# GS_01_Core.net
KiCad netlist of a schematic drawn in Altium Designer
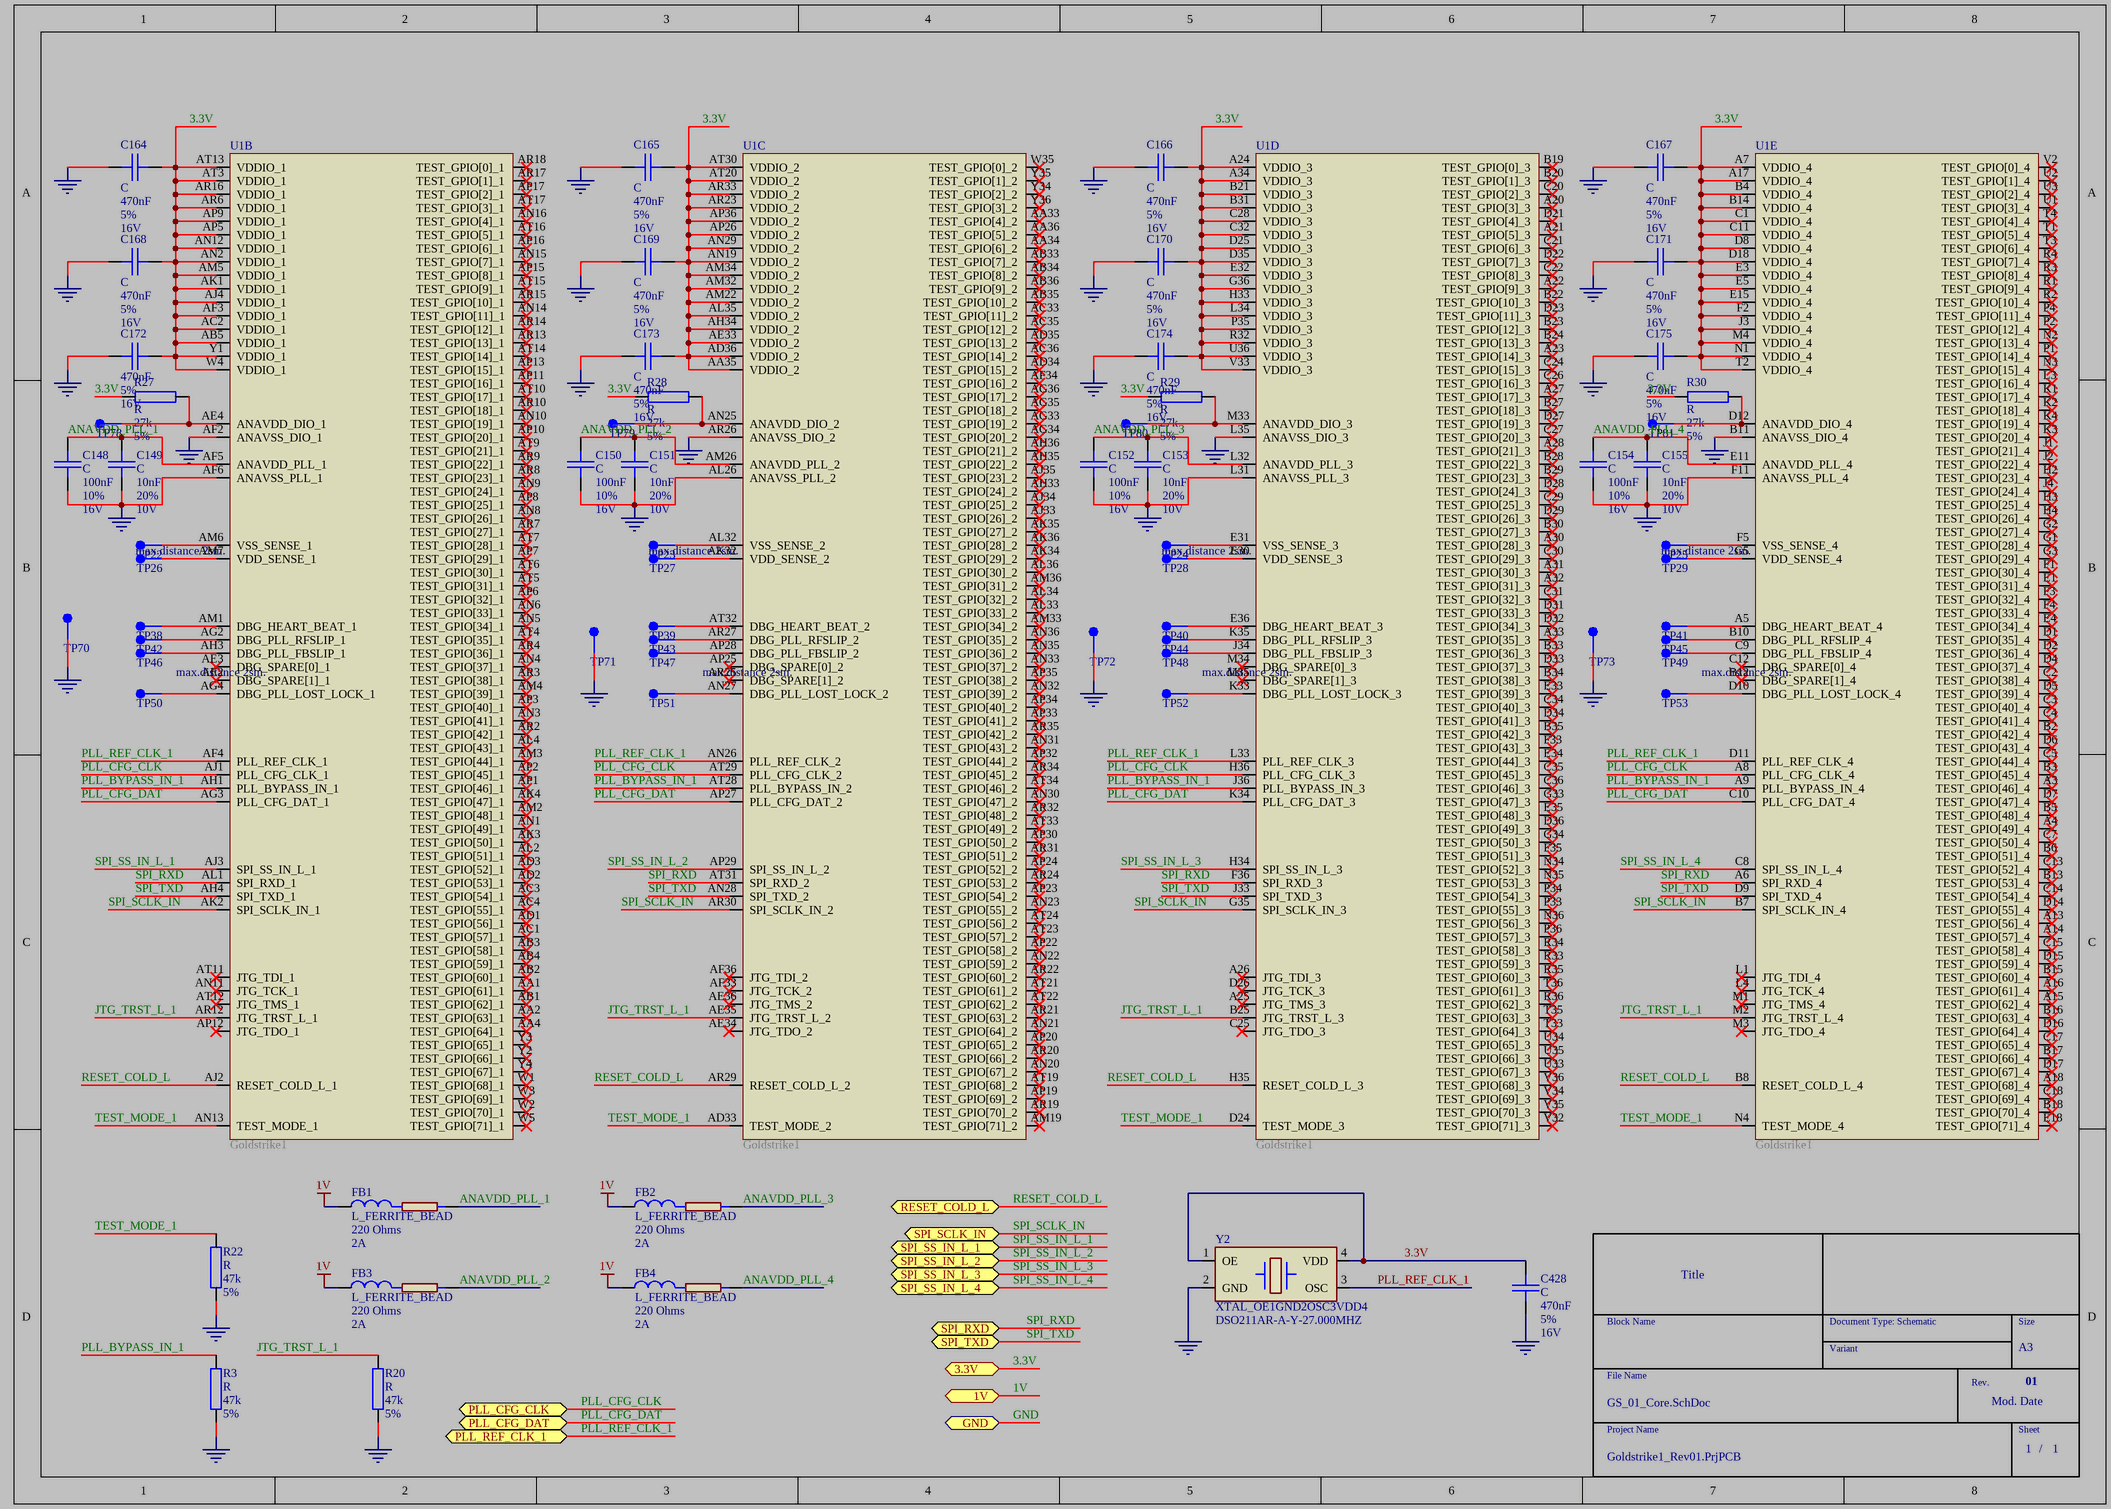
[diagram p0: GS_01_Core.SchDoc]

(export (version "E")
  (design (tool "Eeschema 10.0.6"))
  (components
    (comp (ref "C148")
      (value "C")
      (footprint "SMD_0603_CAPC1608X95N")
      (fields
        (field (name "DB_PART_NUMBER") "CAP000047357")
        (field (name "DB_VALUE") "100nF")
        (field (name "DB_TOLERANCE") "10%")
        (field (name "DB_VOLTAGE") "16V")
        (field (name "DB_MANUFACTURER_PART") "YAGEO      223878615649")
        (field (name "DB_APPROVED_BY") "VSN")
      )
      (libsource (lib "Database_Libs1") (part "C"))
    )
    (comp (ref "C149")
      (value "C")
      (footprint "SMD_0603_CAPC1608X95N")
      (fields
        (field (name "DB_PART_NUMBER") "CAP000038821")
        (field (name "DB_VALUE") "10nF")
        (field (name "DB_TOLERANCE") "20%")
        (field (name "DB_VOLTAGE") "10V")
        (field (name "DB_MANUFACTURER_PART") "KEMET    C0603C103M8GAC")
      )
      (libsource (lib "Database_Libs1") (part "C"))
    )
    (comp (ref "C150")
      (value "C")
      (footprint "SMD_0603_CAPC1608X95N")
      (fields
        (field (name "DB_PART_NUMBER") "CAP000047357")
        (field (name "DB_VALUE") "100nF")
        (field (name "DB_TOLERANCE") "10%")
        (field (name "DB_VOLTAGE") "16V")
        (field (name "DB_MANUFACTURER_PART") "YAGEO      223878615649")
        (field (name "DB_APPROVED_BY") "VSN")
      )
      (libsource (lib "Database_Libs1") (part "C"))
    )
    (comp (ref "C151")
      (value "C")
      (footprint "SMD_0603_CAPC1608X95N")
      (fields
        (field (name "DB_PART_NUMBER") "CAP000038821")
        (field (name "DB_VALUE") "10nF")
        (field (name "DB_TOLERANCE") "20%")
        (field (name "DB_VOLTAGE") "10V")
        (field (name "DB_MANUFACTURER_PART") "KEMET    C0603C103M8GAC")
      )
      (libsource (lib "Database_Libs1") (part "C"))
    )
    (comp (ref "C152")
      (value "C")
      (footprint "SMD_0603_CAPC1608X95N")
      (fields
        (field (name "DB_PART_NUMBER") "CAP000047357")
        (field (name "DB_VALUE") "100nF")
        (field (name "DB_TOLERANCE") "10%")
        (field (name "DB_VOLTAGE") "16V")
        (field (name "DB_MANUFACTURER_PART") "YAGEO      223878615649")
        (field (name "DB_APPROVED_BY") "VSN")
      )
      (libsource (lib "Database_Libs1") (part "C"))
    )
    (comp (ref "C153")
      (value "C")
      (footprint "SMD_0603_CAPC1608X95N")
      (fields
        (field (name "DB_PART_NUMBER") "CAP000038821")
        (field (name "DB_VALUE") "10nF")
        (field (name "DB_TOLERANCE") "20%")
        (field (name "DB_VOLTAGE") "10V")
        (field (name "DB_MANUFACTURER_PART") "KEMET    C0603C103M8GAC")
      )
      (libsource (lib "Database_Libs1") (part "C"))
    )
    (comp (ref "C154")
      (value "C")
      (footprint "SMD_0603_CAPC1608X95N")
      (fields
        (field (name "DB_PART_NUMBER") "CAP000047357")
        (field (name "DB_VALUE") "100nF")
        (field (name "DB_TOLERANCE") "10%")
        (field (name "DB_VOLTAGE") "16V")
        (field (name "DB_MANUFACTURER_PART") "YAGEO      223878615649")
        (field (name "DB_APPROVED_BY") "VSN")
      )
      (libsource (lib "Database_Libs1") (part "C"))
    )
    (comp (ref "C155")
      (value "C")
      (footprint "SMD_0603_CAPC1608X95N")
      (fields
        (field (name "DB_PART_NUMBER") "CAP000038821")
        (field (name "DB_VALUE") "10nF")
        (field (name "DB_TOLERANCE") "20%")
        (field (name "DB_VOLTAGE") "10V")
        (field (name "DB_MANUFACTURER_PART") "KEMET    C0603C103M8GAC")
      )
      (libsource (lib "Database_Libs1") (part "C"))
    )
    (comp (ref "C164")
      (value "C")
      (footprint "SMD_0603_CAPC1608X95N")
      (fields
        (field (name "DB_PART_NUMBER") "CAP000028169")
        (field (name "DB_VALUE") "470nF")
        (field (name "DB_TOLERANCE") "5%")
        (field (name "DB_VOLTAGE") "16V")
        (field (name "DB_MANUFACTURER_PART") "KEMET    C0603C474J4RAC")
      )
      (libsource (lib "Database_Libs1") (part "C"))
    )
    (comp (ref "C165")
      (value "C")
      (footprint "SMD_0603_CAPC1608X95N")
      (fields
        (field (name "DB_PART_NUMBER") "CAP000028169")
        (field (name "DB_VALUE") "470nF")
        (field (name "DB_TOLERANCE") "5%")
        (field (name "DB_VOLTAGE") "16V")
        (field (name "DB_MANUFACTURER_PART") "KEMET    C0603C474J4RAC")
      )
      (libsource (lib "Database_Libs1") (part "C"))
    )
    (comp (ref "C166")
      (value "C")
      (footprint "SMD_0603_CAPC1608X95N")
      (fields
        (field (name "DB_PART_NUMBER") "CAP000028169")
        (field (name "DB_VALUE") "470nF")
        (field (name "DB_TOLERANCE") "5%")
        (field (name "DB_VOLTAGE") "16V")
        (field (name "DB_MANUFACTURER_PART") "KEMET    C0603C474J4RAC")
      )
      (libsource (lib "Database_Libs1") (part "C"))
    )
    (comp (ref "C167")
      (value "C")
      (footprint "SMD_0603_CAPC1608X95N")
      (fields
        (field (name "DB_PART_NUMBER") "CAP000028169")
        (field (name "DB_VALUE") "470nF")
        (field (name "DB_TOLERANCE") "5%")
        (field (name "DB_VOLTAGE") "16V")
        (field (name "DB_MANUFACTURER_PART") "KEMET    C0603C474J4RAC")
      )
      (libsource (lib "Database_Libs1") (part "C"))
    )
    (comp (ref "C168")
      (value "C")
      (footprint "SMD_0603_CAPC1608X95N")
      (fields
        (field (name "DB_PART_NUMBER") "CAP000028169")
        (field (name "DB_VALUE") "470nF")
        (field (name "DB_TOLERANCE") "5%")
        (field (name "DB_VOLTAGE") "16V")
        (field (name "DB_MANUFACTURER_PART") "KEMET    C0603C474J4RAC")
      )
      (libsource (lib "Database_Libs1") (part "C"))
    )
    (comp (ref "C169")
      (value "C")
      (footprint "SMD_0603_CAPC1608X95N")
      (fields
        (field (name "DB_PART_NUMBER") "CAP000028169")
        (field (name "DB_VALUE") "470nF")
        (field (name "DB_TOLERANCE") "5%")
        (field (name "DB_VOLTAGE") "16V")
        (field (name "DB_MANUFACTURER_PART") "KEMET    C0603C474J4RAC")
      )
      (libsource (lib "Database_Libs1") (part "C"))
    )
    (comp (ref "C170")
      (value "C")
      (footprint "SMD_0603_CAPC1608X95N")
      (fields
        (field (name "DB_PART_NUMBER") "CAP000028169")
        (field (name "DB_VALUE") "470nF")
        (field (name "DB_TOLERANCE") "5%")
        (field (name "DB_VOLTAGE") "16V")
        (field (name "DB_MANUFACTURER_PART") "KEMET    C0603C474J4RAC")
      )
      (libsource (lib "Database_Libs1") (part "C"))
    )
    (comp (ref "C171")
      (value "C")
      (footprint "SMD_0603_CAPC1608X95N")
      (fields
        (field (name "DB_PART_NUMBER") "CAP000028169")
        (field (name "DB_VALUE") "470nF")
        (field (name "DB_TOLERANCE") "5%")
        (field (name "DB_VOLTAGE") "16V")
        (field (name "DB_MANUFACTURER_PART") "KEMET    C0603C474J4RAC")
      )
      (libsource (lib "Database_Libs1") (part "C"))
    )
    (comp (ref "C172")
      (value "C")
      (footprint "SMD_0603_CAPC1608X95N")
      (fields
        (field (name "DB_PART_NUMBER") "CAP000028169")
        (field (name "DB_VALUE") "470nF")
        (field (name "DB_TOLERANCE") "5%")
        (field (name "DB_VOLTAGE") "16V")
        (field (name "DB_MANUFACTURER_PART") "KEMET    C0603C474J4RAC")
      )
      (libsource (lib "Database_Libs1") (part "C"))
    )
    (comp (ref "C173")
      (value "C")
      (footprint "SMD_0603_CAPC1608X95N")
      (fields
        (field (name "DB_PART_NUMBER") "CAP000028169")
        (field (name "DB_VALUE") "470nF")
        (field (name "DB_TOLERANCE") "5%")
        (field (name "DB_VOLTAGE") "16V")
        (field (name "DB_MANUFACTURER_PART") "KEMET    C0603C474J4RAC")
      )
      (libsource (lib "Database_Libs1") (part "C"))
    )
    (comp (ref "C174")
      (value "C")
      (footprint "SMD_0603_CAPC1608X95N")
      (fields
        (field (name "DB_PART_NUMBER") "CAP000028169")
        (field (name "DB_VALUE") "470nF")
        (field (name "DB_TOLERANCE") "5%")
        (field (name "DB_VOLTAGE") "16V")
        (field (name "DB_MANUFACTURER_PART") "KEMET    C0603C474J4RAC")
      )
      (libsource (lib "Database_Libs1") (part "C"))
    )
    (comp (ref "C175")
      (value "C")
      (footprint "SMD_0603_CAPC1608X95N")
      (fields
        (field (name "DB_PART_NUMBER") "CAP000028169")
        (field (name "DB_VALUE") "470nF")
        (field (name "DB_TOLERANCE") "5%")
        (field (name "DB_VOLTAGE") "16V")
        (field (name "DB_MANUFACTURER_PART") "KEMET    C0603C474J4RAC")
      )
      (libsource (lib "Database_Libs1") (part "C"))
    )
    (comp (ref "C428")
      (value "C")
      (footprint "SMD_0603_CAPC1608X95N")
      (fields
        (field (name "DB_PART_NUMBER") "CAP000028169")
        (field (name "DB_VALUE") "470nF")
        (field (name "DB_TOLERANCE") "5%")
        (field (name "DB_VOLTAGE") "16V")
        (field (name "DB_MANUFACTURER_PART") "KEMET    C0603C474J4RAC")
      )
      (libsource (lib "Database_Libs1") (part "C"))
    )
    (comp (ref "FB1")
      (value "L_FERRITE_BEAD")
      (footprint "SMD_0805_INDC2012X105N")
      (fields
        (field (name "DB_PART_NUMBER") "IND000000029")
        (field (name "DB_VALUE") "220 Ohms")
        (field (name "DB_CURRENT") "2A")
        (field (name "DB_MANUFACTURER_PART") "MURATA       BLM21PG221SN1D")
        (field (name "DB_APPROVED_BY") "VSN")
      )
      (libsource (lib "Database_Libs1") (part "L_FERRITE_BEAD"))
    )
    (comp (ref "FB2")
      (value "L_FERRITE_BEAD")
      (footprint "SMD_0805_INDC2012X105N")
      (fields
        (field (name "DB_PART_NUMBER") "IND000000029")
        (field (name "DB_VALUE") "220 Ohms")
        (field (name "DB_CURRENT") "2A")
        (field (name "DB_MANUFACTURER_PART") "MURATA       BLM21PG221SN1D")
        (field (name "DB_APPROVED_BY") "VSN")
      )
      (libsource (lib "Database_Libs1") (part "L_FERRITE_BEAD"))
    )
    (comp (ref "FB3")
      (value "L_FERRITE_BEAD")
      (footprint "SMD_0805_INDC2012X105N")
      (fields
        (field (name "DB_PART_NUMBER") "IND000000029")
        (field (name "DB_VALUE") "220 Ohms")
        (field (name "DB_CURRENT") "2A")
        (field (name "DB_MANUFACTURER_PART") "MURATA       BLM21PG221SN1D")
        (field (name "DB_APPROVED_BY") "VSN")
      )
      (libsource (lib "Database_Libs1") (part "L_FERRITE_BEAD"))
    )
    (comp (ref "FB4")
      (value "L_FERRITE_BEAD")
      (footprint "SMD_0805_INDC2012X105N")
      (fields
        (field (name "DB_PART_NUMBER") "IND000000029")
        (field (name "DB_VALUE") "220 Ohms")
        (field (name "DB_CURRENT") "2A")
        (field (name "DB_MANUFACTURER_PART") "MURATA       BLM21PG221SN1D")
        (field (name "DB_APPROVED_BY") "VSN")
      )
      (libsource (lib "Database_Libs1") (part "L_FERRITE_BEAD"))
    )
    (comp (ref "R3")
      (value "R")
      (footprint "SMD_0603_RESC1608X55N")
      (fields
        (field (name "DB_PART_NUMBER") "RES000006462")
        (field (name "DB_VALUE") "47k")
        (field (name "DB_TOLERANCE") "5%")
        (field (name "DB_MANUFACTURER_PART") "YAGEO    RC0603JR-0747K")
      )
      (libsource (lib "Database_Libs1") (part "R"))
    )
    (comp (ref "R20")
      (value "R")
      (footprint "SMD_0603_RESC1608X55N")
      (fields
        (field (name "DB_PART_NUMBER") "RES000006462")
        (field (name "DB_VALUE") "47k")
        (field (name "DB_TOLERANCE") "5%")
        (field (name "DB_MANUFACTURER_PART") "YAGEO    RC0603JR-0747K")
      )
      (libsource (lib "Database_Libs1") (part "R"))
    )
    (comp (ref "R22")
      (value "R")
      (footprint "SMD_0603_RESC1608X55N")
      (fields
        (field (name "DB_PART_NUMBER") "RES000006462")
        (field (name "DB_VALUE") "47k")
        (field (name "DB_TOLERANCE") "5%")
        (field (name "DB_MANUFACTURER_PART") "YAGEO    RC0603JR-0747K")
      )
      (libsource (lib "Database_Libs1") (part "R"))
    )
    (comp (ref "R27")
      (value "R")
      (footprint "SMD_0603_RESC1608X55N")
      (fields
        (field (name "DB_PART_NUMBER") "RES000006456")
        (field (name "DB_VALUE") "27k")
        (field (name "DB_TOLERANCE") "5%")
        (field (name "DB_MANUFACTURER_PART") "YAGEO    RC0603JR-0727K")
      )
      (libsource (lib "Database_Libs1") (part "R"))
    )
    (comp (ref "R28")
      (value "R")
      (footprint "SMD_0603_RESC1608X55N")
      (fields
        (field (name "DB_PART_NUMBER") "RES000006456")
        (field (name "DB_VALUE") "27k")
        (field (name "DB_TOLERANCE") "5%")
        (field (name "DB_MANUFACTURER_PART") "YAGEO    RC0603JR-0727K")
      )
      (libsource (lib "Database_Libs1") (part "R"))
    )
    (comp (ref "R29")
      (value "R")
      (footprint "SMD_0603_RESC1608X55N")
      (fields
        (field (name "DB_PART_NUMBER") "RES000006456")
        (field (name "DB_VALUE") "27k")
        (field (name "DB_TOLERANCE") "5%")
        (field (name "DB_MANUFACTURER_PART") "YAGEO    RC0603JR-0727K")
      )
      (libsource (lib "Database_Libs1") (part "R"))
    )
    (comp (ref "R30")
      (value "R")
      (footprint "SMD_0603_RESC1608X55N")
      (fields
        (field (name "DB_PART_NUMBER") "RES000006456")
        (field (name "DB_VALUE") "27k")
        (field (name "DB_TOLERANCE") "5%")
        (field (name "DB_MANUFACTURER_PART") "YAGEO    RC0603JR-0727K")
      )
      (libsource (lib "Database_Libs1") (part "R"))
    )
    (comp (ref "TP22")
      (value "TEST_POINT_1")
      (footprint "SMD_TP_100-254")
      (fields (field (name "DB_PART_NUMBER") "TPO000000001"))
      (libsource (lib "Database_Libs1") (part "TEST_POINT_1"))
    )
    (comp (ref "TP23")
      (value "TEST_POINT_1")
      (footprint "SMD_TP_100-254")
      (fields (field (name "DB_PART_NUMBER") "TPO000000001"))
      (libsource (lib "Database_Libs1") (part "TEST_POINT_1"))
    )
    (comp (ref "TP24")
      (value "TEST_POINT_1")
      (footprint "SMD_TP_100-254")
      (fields (field (name "DB_PART_NUMBER") "TPO000000001"))
      (libsource (lib "Database_Libs1") (part "TEST_POINT_1"))
    )
    (comp (ref "TP25")
      (value "TEST_POINT_1")
      (footprint "SMD_TP_100-254")
      (fields (field (name "DB_PART_NUMBER") "TPO000000001"))
      (libsource (lib "Database_Libs1") (part "TEST_POINT_1"))
    )
    (comp (ref "TP26")
      (value "TEST_POINT_1")
      (footprint "SMD_TP_100-254")
      (fields (field (name "DB_PART_NUMBER") "TPO000000001"))
      (libsource (lib "Database_Libs1") (part "TEST_POINT_1"))
    )
    (comp (ref "TP27")
      (value "TEST_POINT_1")
      (footprint "SMD_TP_100-254")
      (fields (field (name "DB_PART_NUMBER") "TPO000000001"))
      (libsource (lib "Database_Libs1") (part "TEST_POINT_1"))
    )
    (comp (ref "TP28")
      (value "TEST_POINT_1")
      (footprint "SMD_TP_100-254")
      (fields (field (name "DB_PART_NUMBER") "TPO000000001"))
      (libsource (lib "Database_Libs1") (part "TEST_POINT_1"))
    )
    (comp (ref "TP29")
      (value "TEST_POINT_1")
      (footprint "SMD_TP_100-254")
      (fields (field (name "DB_PART_NUMBER") "TPO000000001"))
      (libsource (lib "Database_Libs1") (part "TEST_POINT_1"))
    )
    (comp (ref "TP38")
      (value "TEST_POINT_1")
      (footprint "SMD_TP_100-254")
      (fields (field (name "DB_PART_NUMBER") "TPO000000001"))
      (libsource (lib "Database_Libs1") (part "TEST_POINT_1"))
    )
    (comp (ref "TP39")
      (value "TEST_POINT_1")
      (footprint "SMD_TP_100-254")
      (fields (field (name "DB_PART_NUMBER") "TPO000000001"))
      (libsource (lib "Database_Libs1") (part "TEST_POINT_1"))
    )
    (comp (ref "TP40")
      (value "TEST_POINT_1")
      (footprint "SMD_TP_100-254")
      (fields (field (name "DB_PART_NUMBER") "TPO000000001"))
      (libsource (lib "Database_Libs1") (part "TEST_POINT_1"))
    )
    (comp (ref "TP41")
      (value "TEST_POINT_1")
      (footprint "SMD_TP_100-254")
      (fields (field (name "DB_PART_NUMBER") "TPO000000001"))
      (libsource (lib "Database_Libs1") (part "TEST_POINT_1"))
    )
    (comp (ref "TP42")
      (value "TEST_POINT_1")
      (footprint "SMD_TP_100-254")
      (fields (field (name "DB_PART_NUMBER") "TPO000000001"))
      (libsource (lib "Database_Libs1") (part "TEST_POINT_1"))
    )
    (comp (ref "TP43")
      (value "TEST_POINT_1")
      (footprint "SMD_TP_100-254")
      (fields (field (name "DB_PART_NUMBER") "TPO000000001"))
      (libsource (lib "Database_Libs1") (part "TEST_POINT_1"))
    )
    (comp (ref "TP44")
      (value "TEST_POINT_1")
      (footprint "SMD_TP_100-254")
      (fields (field (name "DB_PART_NUMBER") "TPO000000001"))
      (libsource (lib "Database_Libs1") (part "TEST_POINT_1"))
    )
    (comp (ref "TP45")
      (value "TEST_POINT_1")
      (footprint "SMD_TP_100-254")
      (fields (field (name "DB_PART_NUMBER") "TPO000000001"))
      (libsource (lib "Database_Libs1") (part "TEST_POINT_1"))
    )
    (comp (ref "TP46")
      (value "TEST_POINT_1")
      (footprint "SMD_TP_100-254")
      (fields (field (name "DB_PART_NUMBER") "TPO000000001"))
      (libsource (lib "Database_Libs1") (part "TEST_POINT_1"))
    )
    (comp (ref "TP47")
      (value "TEST_POINT_1")
      (footprint "SMD_TP_100-254")
      (fields (field (name "DB_PART_NUMBER") "TPO000000001"))
      (libsource (lib "Database_Libs1") (part "TEST_POINT_1"))
    )
    (comp (ref "TP48")
      (value "TEST_POINT_1")
      (footprint "SMD_TP_100-254")
      (fields (field (name "DB_PART_NUMBER") "TPO000000001"))
      (libsource (lib "Database_Libs1") (part "TEST_POINT_1"))
    )
    (comp (ref "TP49")
      (value "TEST_POINT_1")
      (footprint "SMD_TP_100-254")
      (fields (field (name "DB_PART_NUMBER") "TPO000000001"))
      (libsource (lib "Database_Libs1") (part "TEST_POINT_1"))
    )
    (comp (ref "TP50")
      (value "TEST_POINT_1")
      (footprint "SMD_TP_100-254")
      (fields (field (name "DB_PART_NUMBER") "TPO000000001"))
      (libsource (lib "Database_Libs1") (part "TEST_POINT_1"))
    )
    (comp (ref "TP51")
      (value "TEST_POINT_1")
      (footprint "SMD_TP_100-254")
      (fields (field (name "DB_PART_NUMBER") "TPO000000001"))
      (libsource (lib "Database_Libs1") (part "TEST_POINT_1"))
    )
    (comp (ref "TP52")
      (value "TEST_POINT_1")
      (footprint "SMD_TP_100-254")
      (fields (field (name "DB_PART_NUMBER") "TPO000000001"))
      (libsource (lib "Database_Libs1") (part "TEST_POINT_1"))
    )
    (comp (ref "TP53")
      (value "TEST_POINT_1")
      (footprint "SMD_TP_100-254")
      (fields (field (name "DB_PART_NUMBER") "TPO000000001"))
      (libsource (lib "Database_Libs1") (part "TEST_POINT_1"))
    )
    (comp (ref "TP70")
      (value "TEST_POINT_1")
      (footprint "SMD_TP_100-254")
      (fields (field (name "DB_PART_NUMBER") "TPO000000001"))
      (libsource (lib "Database_Libs1") (part "TEST_POINT_1"))
    )
    (comp (ref "TP71")
      (value "TEST_POINT_1")
      (footprint "SMD_TP_100-254")
      (fields (field (name "DB_PART_NUMBER") "TPO000000001"))
      (libsource (lib "Database_Libs1") (part "TEST_POINT_1"))
    )
    (comp (ref "TP72")
      (value "TEST_POINT_1")
      (footprint "SMD_TP_100-254")
      (fields (field (name "DB_PART_NUMBER") "TPO000000001"))
      (libsource (lib "Database_Libs1") (part "TEST_POINT_1"))
    )
    (comp (ref "TP73")
      (value "TEST_POINT_1")
      (footprint "SMD_TP_100-254")
      (fields (field (name "DB_PART_NUMBER") "TPO000000001"))
      (libsource (lib "Database_Libs1") (part "TEST_POINT_1"))
    )
    (comp (ref "TP78")
      (value "TEST_POINT_1")
      (footprint "SMD_TP_100-254")
      (fields (field (name "DB_PART_NUMBER") "TPO000000001"))
      (libsource (lib "Database_Libs1") (part "TEST_POINT_1"))
    )
    (comp (ref "TP79")
      (value "TEST_POINT_1")
      (footprint "SMD_TP_100-254")
      (fields (field (name "DB_PART_NUMBER") "TPO000000001"))
      (libsource (lib "Database_Libs1") (part "TEST_POINT_1"))
    )
    (comp (ref "TP80")
      (value "TEST_POINT_1")
      (footprint "SMD_TP_100-254")
      (fields (field (name "DB_PART_NUMBER") "TPO000000001"))
      (libsource (lib "Database_Libs1") (part "TEST_POINT_1"))
    )
    (comp (ref "TP81")
      (value "TEST_POINT_1")
      (footprint "SMD_TP_100-254")
      (fields (field (name "DB_PART_NUMBER") "TPO000000001"))
      (libsource (lib "Database_Libs1") (part "TEST_POINT_1"))
    )
    (comp (ref "U1")
      (value "Goldstrike1")
      (footprint "SMD_BGA1296C100P36X36")
      (libsource (lib "Schlib1") (part "Goldstrike1"))
    )
    (comp (ref "Y2")
      (value "XTAL_OE1GND2OSC3VDD4")
      (footprint "SMD_OSCCC160X200X80-4N")
      (fields
        (field (name "DB_PART_NUMBER") "OSC000000015")
        (field (name "DB_VALUE") "DSO211AR-A-Y-27.000MHZ")
        (field (name "DB_MANUFACTURER_PART") "KDS DAISHINKU      DSO211AR-A-Y-27.000MHZ")
        (field (name "DB_APPROVED_BY") "VSN")
      )
      (libsource (lib "Database_Libs1") (part "XTAL_OE1GND2OSC3VDD4"))
    )
  )
  (nets
    (net (code "1") (name "/3.3V") (class "Default")
      (node (ref "C164") (pin "2") (pinfunction "2_2") (pintype "passive"))
      (node (ref "C165") (pin "2") (pinfunction "2_2") (pintype "passive"))
      (node (ref "C166") (pin "2") (pinfunction "2_2") (pintype "passive"))
      (node (ref "C167") (pin "2") (pinfunction "2_2") (pintype "passive"))
      (node (ref "C168") (pin "2") (pinfunction "2_2") (pintype "passive"))
      (node (ref "C169") (pin "2") (pinfunction "2_2") (pintype "passive"))
      (node (ref "C170") (pin "2") (pinfunction "2_2") (pintype "passive"))
      (node (ref "C171") (pin "2") (pinfunction "2_2") (pintype "passive"))
      (node (ref "C172") (pin "2") (pinfunction "2_2") (pintype "passive"))
      (node (ref "C173") (pin "2") (pinfunction "2_2") (pintype "passive"))
      (node (ref "C174") (pin "2") (pinfunction "2_2") (pintype "passive"))
      (node (ref "C175") (pin "2") (pinfunction "2_2") (pintype "passive"))
      (node (ref "C428") (pin "2") (pinfunction "2_2") (pintype "passive"))
      (node (ref "R27") (pin "1") (pinfunction "1_1") (pintype "passive"))
      (node (ref "R28") (pin "1") (pinfunction "1_1") (pintype "passive"))
      (node (ref "R29") (pin "1") (pinfunction "1_1") (pintype "passive"))
      (node (ref "R30") (pin "1") (pinfunction "1_1") (pintype "passive"))
      (node (ref "U1") (pin "A17") (pinfunction "VDDIO_4_A17") (pintype "passive"))
      (node (ref "U1") (pin "A24") (pinfunction "VDDIO_3_A24") (pintype "passive"))
      (node (ref "U1") (pin "A34") (pinfunction "VDDIO_3_A34") (pintype "passive"))
      (node (ref "U1") (pin "A7") (pinfunction "VDDIO_4_A7") (pintype "passive"))
      (node (ref "U1") (pin "AA35") (pinfunction "VDDIO_2_AA35") (pintype "passive"))
      (node (ref "U1") (pin "AB5") (pinfunction "VDDIO_1_AB5") (pintype "passive"))
      (node (ref "U1") (pin "AC2") (pinfunction "VDDIO_1_AC2") (pintype "passive"))
      (node (ref "U1") (pin "AD36") (pinfunction "VDDIO_2_AD36") (pintype "passive"))
      (node (ref "U1") (pin "AE33") (pinfunction "VDDIO_2_AE33") (pintype "passive"))
      (node (ref "U1") (pin "AF3") (pinfunction "VDDIO_1_AF3") (pintype "passive"))
      (node (ref "U1") (pin "AH34") (pinfunction "VDDIO_2_AH34") (pintype "passive"))
      (node (ref "U1") (pin "AJ4") (pinfunction "VDDIO_1_AJ4") (pintype "passive"))
      (node (ref "U1") (pin "AK1") (pinfunction "VDDIO_1_AK1") (pintype "passive"))
      (node (ref "U1") (pin "AL35") (pinfunction "VDDIO_2_AL35") (pintype "passive"))
      (node (ref "U1") (pin "AM22") (pinfunction "VDDIO_2_AM22") (pintype "passive"))
      (node (ref "U1") (pin "AM32") (pinfunction "VDDIO_2_AM32") (pintype "passive"))
      (node (ref "U1") (pin "AM34") (pinfunction "VDDIO_2_AM34") (pintype "passive"))
      (node (ref "U1") (pin "AM5") (pinfunction "VDDIO_1_AM5") (pintype "passive"))
      (node (ref "U1") (pin "AN12") (pinfunction "VDDIO_1_AN12") (pintype "passive"))
      (node (ref "U1") (pin "AN19") (pinfunction "VDDIO_2_AN19") (pintype "passive"))
      (node (ref "U1") (pin "AN2") (pinfunction "VDDIO_1_AN2") (pintype "passive"))
      (node (ref "U1") (pin "AN29") (pinfunction "VDDIO_2_AN29") (pintype "passive"))
      (node (ref "U1") (pin "AP26") (pinfunction "VDDIO_2_AP26") (pintype "passive"))
      (node (ref "U1") (pin "AP36") (pinfunction "VDDIO_2_AP36") (pintype "passive"))
      (node (ref "U1") (pin "AP5") (pinfunction "VDDIO_1_AP5") (pintype "passive"))
      (node (ref "U1") (pin "AP9") (pinfunction "VDDIO_1_AP9") (pintype "passive"))
      (node (ref "U1") (pin "AR16") (pinfunction "VDDIO_1_AR16") (pintype "passive"))
      (node (ref "U1") (pin "AR23") (pinfunction "VDDIO_2_AR23") (pintype "passive"))
      (node (ref "U1") (pin "AR33") (pinfunction "VDDIO_2_AR33") (pintype "passive"))
      (node (ref "U1") (pin "AR6") (pinfunction "VDDIO_1_AR6") (pintype "passive"))
      (node (ref "U1") (pin "AT13") (pinfunction "VDDIO_1_AT13") (pintype "passive"))
      (node (ref "U1") (pin "AT20") (pinfunction "VDDIO_2_AT20") (pintype "passive"))
      (node (ref "U1") (pin "AT3") (pinfunction "VDDIO_1_AT3") (pintype "passive"))
      (node (ref "U1") (pin "AT30") (pinfunction "VDDIO_2_AT30") (pintype "passive"))
      (node (ref "U1") (pin "B14") (pinfunction "VDDIO_4_B14") (pintype "passive"))
      (node (ref "U1") (pin "B21") (pinfunction "VDDIO_3_B21") (pintype "passive"))
      (node (ref "U1") (pin "B31") (pinfunction "VDDIO_3_B31") (pintype "passive"))
      (node (ref "U1") (pin "B4") (pinfunction "VDDIO_4_B4") (pintype "passive"))
      (node (ref "U1") (pin "C1") (pinfunction "VDDIO_4_C1") (pintype "passive"))
      (node (ref "U1") (pin "C11") (pinfunction "VDDIO_4_C11") (pintype "passive"))
      (node (ref "U1") (pin "C28") (pinfunction "VDDIO_3_C28") (pintype "passive"))
      (node (ref "U1") (pin "C32") (pinfunction "VDDIO_3_C32") (pintype "passive"))
      (node (ref "U1") (pin "D18") (pinfunction "VDDIO_4_D18") (pintype "passive"))
      (node (ref "U1") (pin "D25") (pinfunction "VDDIO_3_D25") (pintype "passive"))
      (node (ref "U1") (pin "D35") (pinfunction "VDDIO_3_D35") (pintype "passive"))
      (node (ref "U1") (pin "D8") (pinfunction "VDDIO_4_D8") (pintype "passive"))
      (node (ref "U1") (pin "E15") (pinfunction "VDDIO_4_E15") (pintype "passive"))
      (node (ref "U1") (pin "E3") (pinfunction "VDDIO_4_E3") (pintype "passive"))
      (node (ref "U1") (pin "E32") (pinfunction "VDDIO_3_E32") (pintype "passive"))
      (node (ref "U1") (pin "E5") (pinfunction "VDDIO_4_E5") (pintype "passive"))
      (node (ref "U1") (pin "F2") (pinfunction "VDDIO_4_F2") (pintype "passive"))
      (node (ref "U1") (pin "G36") (pinfunction "VDDIO_3_G36") (pintype "passive"))
      (node (ref "U1") (pin "H33") (pinfunction "VDDIO_3_H33") (pintype "passive"))
      (node (ref "U1") (pin "J3") (pinfunction "VDDIO_4_J3") (pintype "passive"))
      (node (ref "U1") (pin "L34") (pinfunction "VDDIO_3_L34") (pintype "passive"))
      (node (ref "U1") (pin "M4") (pinfunction "VDDIO_4_M4") (pintype "passive"))
      (node (ref "U1") (pin "N1") (pinfunction "VDDIO_4_N1") (pintype "passive"))
      (node (ref "U1") (pin "P35") (pinfunction "VDDIO_3_P35") (pintype "passive"))
      (node (ref "U1") (pin "R32") (pinfunction "VDDIO_3_R32") (pintype "passive"))
      (node (ref "U1") (pin "T2") (pinfunction "VDDIO_4_T2") (pintype "passive"))
      (node (ref "U1") (pin "U36") (pinfunction "VDDIO_3_U36") (pintype "passive"))
      (node (ref "U1") (pin "V33") (pinfunction "VDDIO_3_V33") (pintype "passive"))
      (node (ref "U1") (pin "W4") (pinfunction "VDDIO_1_W4") (pintype "passive"))
      (node (ref "U1") (pin "Y1") (pinfunction "VDDIO_1_Y1") (pintype "passive"))
      (node (ref "Y2") (pin "1") (pinfunction "OE_1") (pintype "passive"))
      (node (ref "Y2") (pin "4") (pinfunction "VDD_4") (pintype "passive"))
    )
    (net (code "2") (name "/ANAVDD_PLL_1") (class "Default")
      (node (ref "C148") (pin "1") (pinfunction "1_1") (pintype "passive"))
      (node (ref "C149") (pin "1") (pinfunction "1_1") (pintype "passive"))
      (node (ref "FB1") (pin "2") (pinfunction "2_2") (pintype "passive"))
      (node (ref "U1") (pin "AF5") (pinfunction "ANAVDD_PLL_1_AF5") (pintype "passive"))
    )
    (net (code "3") (name "/ANAVDD_PLL_2") (class "Default")
      (node (ref "C150") (pin "1") (pinfunction "1_1") (pintype "passive"))
      (node (ref "C151") (pin "1") (pinfunction "1_1") (pintype "passive"))
      (node (ref "FB3") (pin "2") (pinfunction "2_2") (pintype "passive"))
      (node (ref "U1") (pin "AM26") (pinfunction "ANAVDD_PLL_2_AM26") (pintype "passive"))
    )
    (net (code "4") (name "/ANAVDD_PLL_3") (class "Default")
      (node (ref "C152") (pin "1") (pinfunction "1_1") (pintype "passive"))
      (node (ref "C153") (pin "1") (pinfunction "1_1") (pintype "passive"))
      (node (ref "FB2") (pin "2") (pinfunction "2_2") (pintype "passive"))
      (node (ref "U1") (pin "L32") (pinfunction "ANAVDD_PLL_3_L32") (pintype "passive"))
    )
    (net (code "5") (name "/ANAVDD_PLL_4") (class "Default")
      (node (ref "C154") (pin "1") (pinfunction "1_1") (pintype "passive"))
      (node (ref "C155") (pin "1") (pinfunction "1_1") (pintype "passive"))
      (node (ref "FB4") (pin "2") (pinfunction "2_2") (pintype "passive"))
      (node (ref "U1") (pin "E11") (pinfunction "ANAVDD_PLL_4_E11") (pintype "passive"))
    )
    (net (code "6") (name "/JTG_TRST_L_1") (class "Default")
      (node (ref "R20") (pin "1") (pinfunction "1_1") (pintype "passive"))
      (node (ref "U1") (pin "AE35") (pinfunction "JTG_TRST_L_2_AE35") (pintype "passive"))
      (node (ref "U1") (pin "AR12") (pinfunction "JTG_TRST_L_1_AR12") (pintype "passive"))
      (node (ref "U1") (pin "B25") (pinfunction "JTG_TRST_L_3_B25") (pintype "passive"))
      (node (ref "U1") (pin "M2") (pinfunction "JTG_TRST_L_4_M2") (pintype "passive"))
    )
    (net (code "7") (name "/PLL_BYPASS_IN_1") (class "Default")
      (node (ref "R3") (pin "1") (pinfunction "1_1") (pintype "passive"))
      (node (ref "U1") (pin "A9") (pinfunction "PLL_BYPASS_IN_4_A9") (pintype "passive"))
      (node (ref "U1") (pin "AH1") (pinfunction "PLL_BYPASS_IN_1_AH1") (pintype "passive"))
      (node (ref "U1") (pin "AT28") (pinfunction "PLL_BYPASS_IN_2_AT28") (pintype "passive"))
      (node (ref "U1") (pin "J36") (pinfunction "PLL_BYPASS_IN_3_J36") (pintype "passive"))
    )
    (net (code "8") (name "/PLL_CFG_CLK") (class "Default")
      (node (ref "U1") (pin "A8") (pinfunction "PLL_CFG_CLK_4_A8") (pintype "passive"))
      (node (ref "U1") (pin "AJ1") (pinfunction "PLL_CFG_CLK_1_AJ1") (pintype "passive"))
      (node (ref "U1") (pin "AT29") (pinfunction "PLL_CFG_CLK_2_AT29") (pintype "passive"))
      (node (ref "U1") (pin "H36") (pinfunction "PLL_CFG_CLK_3_H36") (pintype "passive"))
    )
    (net (code "9") (name "/PLL_CFG_DAT") (class "Default")
      (node (ref "U1") (pin "AG3") (pinfunction "PLL_CFG_DAT_1_AG3") (pintype "passive"))
      (node (ref "U1") (pin "AP27") (pinfunction "PLL_CFG_DAT_2_AP27") (pintype "passive"))
      (node (ref "U1") (pin "C10") (pinfunction "PLL_CFG_DAT_4_C10") (pintype "passive"))
      (node (ref "U1") (pin "K34") (pinfunction "PLL_CFG_DAT_3_K34") (pintype "passive"))
    )
    (net (code "10") (name "/PLL_REF_CLK_1") (class "Default")
      (node (ref "U1") (pin "AF4") (pinfunction "PLL_REF_CLK_1_AF4") (pintype "passive"))
      (node (ref "U1") (pin "AN26") (pinfunction "PLL_REF_CLK_2_AN26") (pintype "passive"))
      (node (ref "U1") (pin "D11") (pinfunction "PLL_REF_CLK_4_D11") (pintype "passive"))
      (node (ref "U1") (pin "L33") (pinfunction "PLL_REF_CLK_3_L33") (pintype "passive"))
      (node (ref "Y2") (pin "3") (pinfunction "OSC_3") (pintype "passive"))
    )
    (net (code "11") (name "/RESET_COLD_L") (class "Default")
      (node (ref "U1") (pin "AJ2") (pinfunction "RESET_COLD_L_1_AJ2") (pintype "passive"))
      (node (ref "U1") (pin "AR29") (pinfunction "RESET_COLD_L_2_AR29") (pintype "passive"))
      (node (ref "U1") (pin "B8") (pinfunction "RESET_COLD_L_4_B8") (pintype "passive"))
      (node (ref "U1") (pin "H35") (pinfunction "RESET_COLD_L_3_H35") (pintype "passive"))
    )
    (net (code "12") (name "/SPI_RXD") (class "Default")
      (node (ref "U1") (pin "A6") (pinfunction "SPI_RXD_4_A6") (pintype "passive"))
      (node (ref "U1") (pin "AL1") (pinfunction "SPI_RXD_1_AL1") (pintype "passive"))
      (node (ref "U1") (pin "AT31") (pinfunction "SPI_RXD_2_AT31") (pintype "passive"))
      (node (ref "U1") (pin "F36") (pinfunction "SPI_RXD_3_F36") (pintype "passive"))
    )
    (net (code "13") (name "/SPI_SCLK_IN") (class "Default")
      (node (ref "U1") (pin "AK2") (pinfunction "SPI_SCLK_IN_1_AK2") (pintype "passive"))
      (node (ref "U1") (pin "AR30") (pinfunction "SPI_SCLK_IN_2_AR30") (pintype "passive"))
      (node (ref "U1") (pin "B7") (pinfunction "SPI_SCLK_IN_4_B7") (pintype "passive"))
      (node (ref "U1") (pin "G35") (pinfunction "SPI_SCLK_IN_3_G35") (pintype "passive"))
    )
    (net (code "14") (name "/SPI_SS_IN_L_1") (class "Default")
      (node (ref "U1") (pin "AJ3") (pinfunction "SPI_SS_IN_L_1_AJ3") (pintype "passive"))
    )
    (net (code "15") (name "/SPI_SS_IN_L_2") (class "Default")
      (node (ref "U1") (pin "AP29") (pinfunction "SPI_SS_IN_L_2_AP29") (pintype "passive"))
    )
    (net (code "16") (name "/SPI_SS_IN_L_3") (class "Default")
      (node (ref "U1") (pin "H34") (pinfunction "SPI_SS_IN_L_3_H34") (pintype "passive"))
    )
    (net (code "17") (name "/SPI_SS_IN_L_4") (class "Default")
      (node (ref "U1") (pin "C8") (pinfunction "SPI_SS_IN_L_4_C8") (pintype "passive"))
    )
    (net (code "18") (name "/SPI_TXD") (class "Default")
      (node (ref "U1") (pin "AH4") (pinfunction "SPI_TXD_1_AH4") (pintype "passive"))
      (node (ref "U1") (pin "AN28") (pinfunction "SPI_TXD_2_AN28") (pintype "passive"))
      (node (ref "U1") (pin "D9") (pinfunction "SPI_TXD_4_D9") (pintype "passive"))
      (node (ref "U1") (pin "J33") (pinfunction "SPI_TXD_3_J33") (pintype "passive"))
    )
    (net (code "19") (name "/TEST_MODE_1") (class "Default")
      (node (ref "R22") (pin "1") (pinfunction "1_1") (pintype "passive"))
      (node (ref "U1") (pin "AD33") (pinfunction "TEST_MODE_2_AD33") (pintype "passive"))
      (node (ref "U1") (pin "AN13") (pinfunction "TEST_MODE_1_AN13") (pintype "passive"))
      (node (ref "U1") (pin "D24") (pinfunction "TEST_MODE_3_D24") (pintype "passive"))
      (node (ref "U1") (pin "N4") (pinfunction "TEST_MODE_4_N4") (pintype "passive"))
    )
    (net (code "20") (name "1V") (class "Default")
      (node (ref "FB1") (pin "1") (pinfunction "1_1") (pintype "passive"))
      (node (ref "FB2") (pin "1") (pinfunction "1_1") (pintype "passive"))
      (node (ref "FB3") (pin "1") (pinfunction "1_1") (pintype "passive"))
      (node (ref "FB4") (pin "1") (pinfunction "1_1") (pintype "passive"))
    )
    (net (code "21") (name "GND") (class "Default")
      (node (ref "C148") (pin "2") (pinfunction "2_2") (pintype "passive"))
      (node (ref "C149") (pin "2") (pinfunction "2_2") (pintype "passive"))
      (node (ref "C150") (pin "2") (pinfunction "2_2") (pintype "passive"))
      (node (ref "C151") (pin "2") (pinfunction "2_2") (pintype "passive"))
      (node (ref "C152") (pin "2") (pinfunction "2_2") (pintype "passive"))
      (node (ref "C153") (pin "2") (pinfunction "2_2") (pintype "passive"))
      (node (ref "C154") (pin "2") (pinfunction "2_2") (pintype "passive"))
      (node (ref "C155") (pin "2") (pinfunction "2_2") (pintype "passive"))
      (node (ref "C164") (pin "1") (pinfunction "1_1") (pintype "passive"))
      (node (ref "C165") (pin "1") (pinfunction "1_1") (pintype "passive"))
      (node (ref "C166") (pin "1") (pinfunction "1_1") (pintype "passive"))
      (node (ref "C167") (pin "1") (pinfunction "1_1") (pintype "passive"))
      (node (ref "C168") (pin "1") (pinfunction "1_1") (pintype "passive"))
      (node (ref "C169") (pin "1") (pinfunction "1_1") (pintype "passive"))
      (node (ref "C170") (pin "1") (pinfunction "1_1") (pintype "passive"))
      (node (ref "C171") (pin "1") (pinfunction "1_1") (pintype "passive"))
      (node (ref "C172") (pin "1") (pinfunction "1_1") (pintype "passive"))
      (node (ref "C173") (pin "1") (pinfunction "1_1") (pintype "passive"))
      (node (ref "C174") (pin "1") (pinfunction "1_1") (pintype "passive"))
      (node (ref "C175") (pin "1") (pinfunction "1_1") (pintype "passive"))
      (node (ref "C428") (pin "1") (pinfunction "1_1") (pintype "passive"))
      (node (ref "R20") (pin "2") (pinfunction "2_2") (pintype "passive"))
      (node (ref "R22") (pin "2") (pinfunction "2_2") (pintype "passive"))
      (node (ref "R3") (pin "2") (pinfunction "2_2") (pintype "passive"))
      (node (ref "TP70") (pin "1") (pinfunction "1_1") (pintype "passive"))
      (node (ref "TP71") (pin "1") (pinfunction "1_1") (pintype "passive"))
      (node (ref "TP72") (pin "1") (pinfunction "1_1") (pintype "passive"))
      (node (ref "TP73") (pin "1") (pinfunction "1_1") (pintype "passive"))
      (node (ref "U1") (pin "AF2") (pinfunction "ANAVSS_DIO_1_AF2") (pintype "passive"))
      (node (ref "U1") (pin "AF6") (pinfunction "ANAVSS_PLL_1_AF6") (pintype "passive"))
      (node (ref "U1") (pin "AL26") (pinfunction "ANAVSS_PLL_2_AL26") (pintype "passive"))
      (node (ref "U1") (pin "AR26") (pinfunction "ANAVSS_DIO_2_AR26") (pintype "passive"))
      (node (ref "U1") (pin "B11") (pinfunction "ANAVSS_DIO_4_B11") (pintype "passive"))
      (node (ref "U1") (pin "F11") (pinfunction "ANAVSS_PLL_4_F11") (pintype "passive"))
      (node (ref "U1") (pin "L31") (pinfunction "ANAVSS_PLL_3_L31") (pintype "passive"))
      (node (ref "U1") (pin "L35") (pinfunction "ANAVSS_DIO_3_L35") (pintype "passive"))
      (node (ref "Y2") (pin "2") (pinfunction "GND_2") (pintype "passive"))
    )
    (net (code "22") (name "Net-(U1B-ANAVDD_DIO_1)") (class "Default")
      (node (ref "R27") (pin "2") (pinfunction "2_2") (pintype "passive"))
      (node (ref "TP78") (pin "1") (pinfunction "1_1") (pintype "passive"))
      (node (ref "U1") (pin "AE4") (pinfunction "ANAVDD_DIO_1_AE4") (pintype "passive"))
    )
    (net (code "23") (name "Net-(U1B-DBG_HEART_BEAT_1)") (class "Default")
      (node (ref "TP38") (pin "1") (pinfunction "1_1") (pintype "passive"))
      (node (ref "U1") (pin "AM1") (pinfunction "DBG_HEART_BEAT_1_AM1") (pintype "passive"))
    )
    (net (code "24") (name "Net-(U1B-DBG_PLL_FBSLIP_1)") (class "Default")
      (node (ref "TP46") (pin "1") (pinfunction "1_1") (pintype "passive"))
      (node (ref "U1") (pin "AH3") (pinfunction "DBG_PLL_FBSLIP_1_AH3") (pintype "passive"))
    )
    (net (code "25") (name "Net-(U1B-DBG_PLL_LOST_LOCK_1)") (class "Default")
      (node (ref "TP50") (pin "1") (pinfunction "1_1") (pintype "passive"))
      (node (ref "U1") (pin "AG4") (pinfunction "DBG_PLL_LOST_LOCK_1_AG4") (pintype "passive"))
    )
    (net (code "26") (name "Net-(U1B-DBG_PLL_RFSLIP_1)") (class "Default")
      (node (ref "TP42") (pin "1") (pinfunction "1_1") (pintype "passive"))
      (node (ref "U1") (pin "AG2") (pinfunction "DBG_PLL_RFSLIP_1_AG2") (pintype "passive"))
    )
    (net (code "27") (name "Net-(U1B-VDD_SENSE_1)") (class "Default")
      (node (ref "TP26") (pin "1") (pinfunction "1_1") (pintype "passive"))
      (node (ref "U1") (pin "AM7") (pinfunction "VDD_SENSE_1_AM7") (pintype "passive"))
    )
    (net (code "28") (name "Net-(U1B-VSS_SENSE_1)") (class "Default")
      (node (ref "TP22") (pin "1") (pinfunction "1_1") (pintype "passive"))
      (node (ref "U1") (pin "AM6") (pinfunction "VSS_SENSE_1_AM6") (pintype "passive"))
    )
    (net (code "29") (name "Net-(U1C-ANAVDD_DIO_2)") (class "Default")
      (node (ref "R28") (pin "2") (pinfunction "2_2") (pintype "passive"))
      (node (ref "TP79") (pin "1") (pinfunction "1_1") (pintype "passive"))
      (node (ref "U1") (pin "AN25") (pinfunction "ANAVDD_DIO_2_AN25") (pintype "passive"))
    )
    (net (code "30") (name "Net-(U1C-DBG_HEART_BEAT_2)") (class "Default")
      (node (ref "TP39") (pin "1") (pinfunction "1_1") (pintype "passive"))
      (node (ref "U1") (pin "AT32") (pinfunction "DBG_HEART_BEAT_2_AT32") (pintype "passive"))
    )
    (net (code "31") (name "Net-(U1C-DBG_PLL_FBSLIP_2)") (class "Default")
      (node (ref "TP47") (pin "1") (pinfunction "1_1") (pintype "passive"))
      (node (ref "U1") (pin "AP28") (pinfunction "DBG_PLL_FBSLIP_2_AP28") (pintype "passive"))
    )
    (net (code "32") (name "Net-(U1C-DBG_PLL_LOST_LOCK_2)") (class "Default")
      (node (ref "TP51") (pin "1") (pinfunction "1_1") (pintype "passive"))
      (node (ref "U1") (pin "AN27") (pinfunction "DBG_PLL_LOST_LOCK_2_AN27") (pintype "passive"))
    )
    (net (code "33") (name "Net-(U1C-DBG_PLL_RFSLIP_2)") (class "Default")
      (node (ref "TP43") (pin "1") (pinfunction "1_1") (pintype "passive"))
      (node (ref "U1") (pin "AR27") (pinfunction "DBG_PLL_RFSLIP_2_AR27") (pintype "passive"))
    )
    (net (code "34") (name "Net-(U1C-VDD_SENSE_2)") (class "Default")
      (node (ref "TP27") (pin "1") (pinfunction "1_1") (pintype "passive"))
      (node (ref "U1") (pin "AK32") (pinfunction "VDD_SENSE_2_AK32") (pintype "passive"))
    )
    (net (code "35") (name "Net-(U1C-VSS_SENSE_2)") (class "Default")
      (node (ref "TP23") (pin "1") (pinfunction "1_1") (pintype "passive"))
      (node (ref "U1") (pin "AL32") (pinfunction "VSS_SENSE_2_AL32") (pintype "passive"))
    )
    (net (code "36") (name "Net-(U1D-ANAVDD_DIO_3)") (class "Default")
      (node (ref "R29") (pin "2") (pinfunction "2_2") (pintype "passive"))
      (node (ref "TP80") (pin "1") (pinfunction "1_1") (pintype "passive"))
      (node (ref "U1") (pin "M33") (pinfunction "ANAVDD_DIO_3_M33") (pintype "passive"))
    )
    (net (code "37") (name "Net-(U1D-DBG_HEART_BEAT_3)") (class "Default")
      (node (ref "TP40") (pin "1") (pinfunction "1_1") (pintype "passive"))
      (node (ref "U1") (pin "E36") (pinfunction "DBG_HEART_BEAT_3_E36") (pintype "passive"))
    )
    (net (code "38") (name "Net-(U1D-DBG_PLL_FBSLIP_3)") (class "Default")
      (node (ref "TP48") (pin "1") (pinfunction "1_1") (pintype "passive"))
      (node (ref "U1") (pin "J34") (pinfunction "DBG_PLL_FBSLIP_3_J34") (pintype "passive"))
    )
    (net (code "39") (name "Net-(U1D-DBG_PLL_LOST_LOCK_3)") (class "Default")
      (node (ref "TP52") (pin "1") (pinfunction "1_1") (pintype "passive"))
      (node (ref "U1") (pin "K33") (pinfunction "DBG_PLL_LOST_LOCK_3_K33") (pintype "passive"))
    )
    (net (code "40") (name "Net-(U1D-DBG_PLL_RFSLIP_3)") (class "Default")
      (node (ref "TP44") (pin "1") (pinfunction "1_1") (pintype "passive"))
      (node (ref "U1") (pin "K35") (pinfunction "DBG_PLL_RFSLIP_3_K35") (pintype "passive"))
    )
    (net (code "41") (name "Net-(U1D-VDD_SENSE_3)") (class "Default")
      (node (ref "TP28") (pin "1") (pinfunction "1_1") (pintype "passive"))
      (node (ref "U1") (pin "E30") (pinfunction "VDD_SENSE_3_E30") (pintype "passive"))
    )
    (net (code "42") (name "Net-(U1D-VSS_SENSE_3)") (class "Default")
      (node (ref "TP24") (pin "1") (pinfunction "1_1") (pintype "passive"))
      (node (ref "U1") (pin "E31") (pinfunction "VSS_SENSE_3_E31") (pintype "passive"))
    )
    (net (code "43") (name "Net-(U1E-ANAVDD_DIO_4)") (class "Default")
      (node (ref "R30") (pin "2") (pinfunction "2_2") (pintype "passive"))
      (node (ref "TP81") (pin "1") (pinfunction "1_1") (pintype "passive"))
      (node (ref "U1") (pin "D12") (pinfunction "ANAVDD_DIO_4_D12") (pintype "passive"))
    )
    (net (code "44") (name "Net-(U1E-DBG_HEART_BEAT_4)") (class "Default")
      (node (ref "TP41") (pin "1") (pinfunction "1_1") (pintype "passive"))
      (node (ref "U1") (pin "A5") (pinfunction "DBG_HEART_BEAT_4_A5") (pintype "passive"))
    )
    (net (code "45") (name "Net-(U1E-DBG_PLL_FBSLIP_4)") (class "Default")
      (node (ref "TP49") (pin "1") (pinfunction "1_1") (pintype "passive"))
      (node (ref "U1") (pin "C9") (pinfunction "DBG_PLL_FBSLIP_4_C9") (pintype "passive"))
    )
    (net (code "46") (name "Net-(U1E-DBG_PLL_LOST_LOCK_4)") (class "Default")
      (node (ref "TP53") (pin "1") (pinfunction "1_1") (pintype "passive"))
      (node (ref "U1") (pin "D10") (pinfunction "DBG_PLL_LOST_LOCK_4_D10") (pintype "passive"))
    )
    (net (code "47") (name "Net-(U1E-DBG_PLL_RFSLIP_4)") (class "Default")
      (node (ref "TP45") (pin "1") (pinfunction "1_1") (pintype "passive"))
      (node (ref "U1") (pin "B10") (pinfunction "DBG_PLL_RFSLIP_4_B10") (pintype "passive"))
    )
    (net (code "48") (name "Net-(U1E-VDD_SENSE_4)") (class "Default")
      (node (ref "TP29") (pin "1") (pinfunction "1_1") (pintype "passive"))
      (node (ref "U1") (pin "G5") (pinfunction "VDD_SENSE_4_G5") (pintype "passive"))
    )
    (net (code "49") (name "Net-(U1E-VSS_SENSE_4)") (class "Default")
      (node (ref "TP25") (pin "1") (pinfunction "1_1") (pintype "passive"))
      (node (ref "U1") (pin "F5") (pinfunction "VSS_SENSE_4_F5") (pintype "passive"))
    )
    (net (code "50") (name "unconnected-(U1B-DBG_SPARE[0]_1-PadAE3)") (class "Default")
      (node (ref "U1") (pin "AE3") (pinfunction "DBG_SPARE[0]_1_AE3") (pintype "passive+no_connect"))
    )
    (net (code "51") (name "unconnected-(U1B-DBG_SPARE[1]_1-PadAE2)") (class "Default")
      (node (ref "U1") (pin "AE2") (pinfunction "DBG_SPARE[1]_1_AE2") (pintype "passive+no_connect"))
    )
    (net (code "52") (name "unconnected-(U1B-JTG_TCK_1-PadAN11)") (class "Default")
      (node (ref "U1") (pin "AN11") (pinfunction "JTG_TCK_1_AN11") (pintype "passive+no_connect"))
    )
    (net (code "53") (name "unconnected-(U1B-JTG_TDI_1-PadAT11)") (class "Default")
      (node (ref "U1") (pin "AT11") (pinfunction "JTG_TDI_1_AT11") (pintype "passive+no_connect"))
    )
    (net (code "54") (name "unconnected-(U1B-JTG_TDO_1-PadAP12)") (class "Default")
      (node (ref "U1") (pin "AP12") (pinfunction "JTG_TDO_1_AP12") (pintype "passive+no_connect"))
    )
    (net (code "55") (name "unconnected-(U1B-JTG_TMS_1-PadAT12)") (class "Default")
      (node (ref "U1") (pin "AT12") (pinfunction "JTG_TMS_1_AT12") (pintype "passive+no_connect"))
    )
    (net (code "56") (name "unconnected-(U1B-TEST_GPIO[0]_1-PadAR18)") (class "Default")
      (node (ref "U1") (pin "AR18") (pinfunction "TEST_GPIO[0]_1_AR18") (pintype "passive+no_connect"))
    )
    (net (code "57") (name "unconnected-(U1B-TEST_GPIO[1]_1-PadAR17)") (class "Default")
      (node (ref "U1") (pin "AR17") (pinfunction "TEST_GPIO[1]_1_AR17") (pintype "passive+no_connect"))
    )
    (net (code "58") (name "unconnected-(U1B-TEST_GPIO[2]_1-PadAP17)") (class "Default")
      (node (ref "U1") (pin "AP17") (pinfunction "TEST_GPIO[2]_1_AP17") (pintype "passive+no_connect"))
    )
    (net (code "59") (name "unconnected-(U1B-TEST_GPIO[3]_1-PadAT17)") (class "Default")
      (node (ref "U1") (pin "AT17") (pinfunction "TEST_GPIO[3]_1_AT17") (pintype "passive+no_connect"))
    )
    (net (code "60") (name "unconnected-(U1B-TEST_GPIO[4]_1-PadAN16)") (class "Default")
      (node (ref "U1") (pin "AN16") (pinfunction "TEST_GPIO[4]_1_AN16") (pintype "passive+no_connect"))
    )
    (net (code "61") (name "unconnected-(U1B-TEST_GPIO[5]_1-PadAT16)") (class "Default")
      (node (ref "U1") (pin "AT16") (pinfunction "TEST_GPIO[5]_1_AT16") (pintype "passive+no_connect"))
    )
    (net (code "62") (name "unconnected-(U1B-TEST_GPIO[6]_1-PadAP16)") (class "Default")
      (node (ref "U1") (pin "AP16") (pinfunction "TEST_GPIO[6]_1_AP16") (pintype "passive+no_connect"))
    )
    (net (code "63") (name "unconnected-(U1B-TEST_GPIO[7]_1-PadAN15)") (class "Default")
      (node (ref "U1") (pin "AN15") (pinfunction "TEST_GPIO[7]_1_AN15") (pintype "passive+no_connect"))
    )
    (net (code "64") (name "unconnected-(U1B-TEST_GPIO[8]_1-PadAP15)") (class "Default")
      (node (ref "U1") (pin "AP15") (pinfunction "TEST_GPIO[8]_1_AP15") (pintype "passive+no_connect"))
    )
    (net (code "65") (name "unconnected-(U1B-TEST_GPIO[9]_1-PadAT15)") (class "Default")
      (node (ref "U1") (pin "AT15") (pinfunction "TEST_GPIO[9]_1_AT15") (pintype "passive+no_connect"))
    )
    (net (code "66") (name "unconnected-(U1B-TEST_GPIO[10]_1-PadAR15)") (class "Default")
      (node (ref "U1") (pin "AR15") (pinfunction "TEST_GPIO[10]_1_AR15") (pintype "passive+no_connect"))
    )
    (net (code "67") (name "unconnected-(U1B-TEST_GPIO[11]_1-PadAN14)") (class "Default")
      (node (ref "U1") (pin "AN14") (pinfunction "TEST_GPIO[11]_1_AN14") (pintype "passive+no_connect"))
    )
    (net (code "68") (name "unconnected-(U1B-TEST_GPIO[12]_1-PadAR14)") (class "Default")
      (node (ref "U1") (pin "AR14") (pinfunction "TEST_GPIO[12]_1_AR14") (pintype "passive+no_connect"))
    )
    (net (code "69") (name "unconnected-(U1B-TEST_GPIO[13]_1-PadAR13)") (class "Default")
      (node (ref "U1") (pin "AR13") (pinfunction "TEST_GPIO[13]_1_AR13") (pintype "passive+no_connect"))
    )
    (net (code "70") (name "unconnected-(U1B-TEST_GPIO[14]_1-PadAT14)") (class "Default")
      (node (ref "U1") (pin "AT14") (pinfunction "TEST_GPIO[14]_1_AT14") (pintype "passive+no_connect"))
    )
    (net (code "71") (name "unconnected-(U1B-TEST_GPIO[15]_1-PadAP13)") (class "Default")
      (node (ref "U1") (pin "AP13") (pinfunction "TEST_GPIO[15]_1_AP13") (pintype "passive+no_connect"))
    )
    (net (code "72") (name "unconnected-(U1B-TEST_GPIO[16]_1-PadAP11)") (class "Default")
      (node (ref "U1") (pin "AP11") (pinfunction "TEST_GPIO[16]_1_AP11") (pintype "passive+no_connect"))
    )
    (net (code "73") (name "unconnected-(U1B-TEST_GPIO[17]_1-PadAT10)") (class "Default")
      (node (ref "U1") (pin "AT10") (pinfunction "TEST_GPIO[17]_1_AT10") (pintype "passive+no_connect"))
    )
    (net (code "74") (name "unconnected-(U1B-TEST_GPIO[18]_1-PadAR10)") (class "Default")
      (node (ref "U1") (pin "AR10") (pinfunction "TEST_GPIO[18]_1_AR10") (pintype "passive+no_connect"))
    )
    (net (code "75") (name "unconnected-(U1B-TEST_GPIO[19]_1-PadAN10)") (class "Default")
      (node (ref "U1") (pin "AN10") (pinfunction "TEST_GPIO[19]_1_AN10") (pintype "passive+no_connect"))
    )
    (net (code "76") (name "unconnected-(U1B-TEST_GPIO[20]_1-PadAP10)") (class "Default")
      (node (ref "U1") (pin "AP10") (pinfunction "TEST_GPIO[20]_1_AP10") (pintype "passive+no_connect"))
    )
    (net (code "77") (name "unconnected-(U1B-TEST_GPIO[21]_1-PadAT9)") (class "Default")
      (node (ref "U1") (pin "AT9") (pinfunction "TEST_GPIO[21]_1_AT9") (pintype "passive+no_connect"))
    )
    (net (code "78") (name "unconnected-(U1B-TEST_GPIO[22]_1-PadAR9)") (class "Default")
      (node (ref "U1") (pin "AR9") (pinfunction "TEST_GPIO[22]_1_AR9") (pintype "passive+no_connect"))
    )
    (net (code "79") (name "unconnected-(U1B-TEST_GPIO[23]_1-PadAR8)") (class "Default")
      (node (ref "U1") (pin "AR8") (pinfunction "TEST_GPIO[23]_1_AR8") (pintype "passive+no_connect"))
    )
    (net (code "80") (name "unconnected-(U1B-TEST_GPIO[24]_1-PadAN9)") (class "Default")
      (node (ref "U1") (pin "AN9") (pinfunction "TEST_GPIO[24]_1_AN9") (pintype "passive+no_connect"))
    )
    (net (code "81") (name "unconnected-(U1B-TEST_GPIO[25]_1-PadAP8)") (class "Default")
      (node (ref "U1") (pin "AP8") (pinfunction "TEST_GPIO[25]_1_AP8") (pintype "passive+no_connect"))
    )
    (net (code "82") (name "unconnected-(U1B-TEST_GPIO[26]_1-PadAN8)") (class "Default")
      (node (ref "U1") (pin "AN8") (pinfunction "TEST_GPIO[26]_1_AN8") (pintype "passive+no_connect"))
    )
    (net (code "83") (name "unconnected-(U1B-TEST_GPIO[27]_1-PadAR7)") (class "Default")
      (node (ref "U1") (pin "AR7") (pinfunction "TEST_GPIO[27]_1_AR7") (pintype "passive+no_connect"))
    )
    (net (code "84") (name "unconnected-(U1B-TEST_GPIO[28]_1-PadAT7)") (class "Default")
      (node (ref "U1") (pin "AT7") (pinfunction "TEST_GPIO[28]_1_AT7") (pintype "passive+no_connect"))
    )
    (net (code "85") (name "unconnected-(U1B-TEST_GPIO[29]_1-PadAP7)") (class "Default")
      (node (ref "U1") (pin "AP7") (pinfunction "TEST_GPIO[29]_1_AP7") (pintype "passive+no_connect"))
    )
    (net (code "86") (name "unconnected-(U1B-TEST_GPIO[30]_1-PadAT6)") (class "Default")
      (node (ref "U1") (pin "AT6") (pinfunction "TEST_GPIO[30]_1_AT6") (pintype "passive+no_connect"))
    )
    (net (code "87") (name "unconnected-(U1B-TEST_GPIO[31]_1-PadAT5)") (class "Default")
      (node (ref "U1") (pin "AT5") (pinfunction "TEST_GPIO[31]_1_AT5") (pintype "passive+no_connect"))
    )
    (net (code "88") (name "unconnected-(U1B-TEST_GPIO[32]_1-PadAP6)") (class "Default")
      (node (ref "U1") (pin "AP6") (pinfunction "TEST_GPIO[32]_1_AP6") (pintype "passive+no_connect"))
    )
    (net (code "89") (name "unconnected-(U1B-TEST_GPIO[33]_1-PadAN6)") (class "Default")
      (node (ref "U1") (pin "AN6") (pinfunction "TEST_GPIO[33]_1_AN6") (pintype "passive+no_connect"))
    )
    (net (code "90") (name "unconnected-(U1B-TEST_GPIO[34]_1-PadAN5)") (class "Default")
      (node (ref "U1") (pin "AN5") (pinfunction "TEST_GPIO[34]_1_AN5") (pintype "passive+no_connect"))
    )
    (net (code "91") (name "unconnected-(U1B-TEST_GPIO[35]_1-PadAT4)") (class "Default")
      (node (ref "U1") (pin "AT4") (pinfunction "TEST_GPIO[35]_1_AT4") (pintype "passive+no_connect"))
    )
    (net (code "92") (name "unconnected-(U1B-TEST_GPIO[36]_1-PadAR4)") (class "Default")
      (node (ref "U1") (pin "AR4") (pinfunction "TEST_GPIO[36]_1_AR4") (pintype "passive+no_connect"))
    )
    (net (code "93") (name "unconnected-(U1B-TEST_GPIO[37]_1-PadAN4)") (class "Default")
      (node (ref "U1") (pin "AN4") (pinfunction "TEST_GPIO[37]_1_AN4") (pintype "passive+no_connect"))
    )
    (net (code "94") (name "unconnected-(U1B-TEST_GPIO[38]_1-PadAR3)") (class "Default")
      (node (ref "U1") (pin "AR3") (pinfunction "TEST_GPIO[38]_1_AR3") (pintype "passive+no_connect"))
    )
    (net (code "95") (name "unconnected-(U1B-TEST_GPIO[39]_1-PadAM4)") (class "Default")
      (node (ref "U1") (pin "AM4") (pinfunction "TEST_GPIO[39]_1_AM4") (pintype "passive+no_connect"))
    )
    (net (code "96") (name "unconnected-(U1B-TEST_GPIO[40]_1-PadAP3)") (class "Default")
      (node (ref "U1") (pin "AP3") (pinfunction "TEST_GPIO[40]_1_AP3") (pintype "passive+no_connect"))
    )
    (net (code "97") (name "unconnected-(U1B-TEST_GPIO[41]_1-PadAN3)") (class "Default")
      (node (ref "U1") (pin "AN3") (pinfunction "TEST_GPIO[41]_1_AN3") (pintype "passive+no_connect"))
    )
    (net (code "98") (name "unconnected-(U1B-TEST_GPIO[42]_1-PadAR2)") (class "Default")
      (node (ref "U1") (pin "AR2") (pinfunction "TEST_GPIO[42]_1_AR2") (pintype "passive+no_connect"))
    )
    (net (code "99") (name "unconnected-(U1B-TEST_GPIO[43]_1-PadAL4)") (class "Default")
      (node (ref "U1") (pin "AL4") (pinfunction "TEST_GPIO[43]_1_AL4") (pintype "passive+no_connect"))
    )
    (net (code "100") (name "unconnected-(U1B-TEST_GPIO[44]_1-PadAM3)") (class "Default")
      (node (ref "U1") (pin "AM3") (pinfunction "TEST_GPIO[44]_1_AM3") (pintype "passive+no_connect"))
    )
    (net (code "101") (name "unconnected-(U1B-TEST_GPIO[45]_1-PadAP2)") (class "Default")
      (node (ref "U1") (pin "AP2") (pinfunction "TEST_GPIO[45]_1_AP2") (pintype "passive+no_connect"))
    )
    (net (code "102") (name "unconnected-(U1B-TEST_GPIO[46]_1-PadAP1)") (class "Default")
      (node (ref "U1") (pin "AP1") (pinfunction "TEST_GPIO[46]_1_AP1") (pintype "passive+no_connect"))
    )
    (net (code "103") (name "unconnected-(U1B-TEST_GPIO[47]_1-PadAK4)") (class "Default")
      (node (ref "U1") (pin "AK4") (pinfunction "TEST_GPIO[47]_1_AK4") (pintype "passive+no_connect"))
    )
    (net (code "104") (name "unconnected-(U1B-TEST_GPIO[48]_1-PadAM2)") (class "Default")
      (node (ref "U1") (pin "AM2") (pinfunction "TEST_GPIO[48]_1_AM2") (pintype "passive+no_connect"))
    )
    (net (code "105") (name "unconnected-(U1B-TEST_GPIO[49]_1-PadAN1)") (class "Default")
      (node (ref "U1") (pin "AN1") (pinfunction "TEST_GPIO[49]_1_AN1") (pintype "passive+no_connect"))
    )
    (net (code "106") (name "unconnected-(U1B-TEST_GPIO[50]_1-PadAK3)") (class "Default")
      (node (ref "U1") (pin "AK3") (pinfunction "TEST_GPIO[50]_1_AK3") (pintype "passive+no_connect"))
    )
    (net (code "107") (name "unconnected-(U1B-TEST_GPIO[51]_1-PadAL2)") (class "Default")
      (node (ref "U1") (pin "AL2") (pinfunction "TEST_GPIO[51]_1_AL2") (pintype "passive+no_connect"))
    )
    (net (code "108") (name "unconnected-(U1B-TEST_GPIO[52]_1-PadAD3)") (class "Default")
      (node (ref "U1") (pin "AD3") (pinfunction "TEST_GPIO[52]_1_AD3") (pintype "passive+no_connect"))
    )
    (net (code "109") (name "unconnected-(U1B-TEST_GPIO[53]_1-PadAD2)") (class "Default")
      (node (ref "U1") (pin "AD2") (pinfunction "TEST_GPIO[53]_1_AD2") (pintype "passive+no_connect"))
    )
    (net (code "110") (name "unconnected-(U1B-TEST_GPIO[54]_1-PadAC3)") (class "Default")
      (node (ref "U1") (pin "AC3") (pinfunction "TEST_GPIO[54]_1_AC3") (pintype "passive+no_connect"))
    )
    (net (code "111") (name "unconnected-(U1B-TEST_GPIO[55]_1-PadAC4)") (class "Default")
      (node (ref "U1") (pin "AC4") (pinfunction "TEST_GPIO[55]_1_AC4") (pintype "passive+no_connect"))
    )
    (net (code "112") (name "unconnected-(U1B-TEST_GPIO[56]_1-PadAD1)") (class "Default")
      (node (ref "U1") (pin "AD1") (pinfunction "TEST_GPIO[56]_1_AD1") (pintype "passive+no_connect"))
    )
    (net (code "113") (name "unconnected-(U1B-TEST_GPIO[57]_1-PadAC1)") (class "Default")
      (node (ref "U1") (pin "AC1") (pinfunction "TEST_GPIO[57]_1_AC1") (pintype "passive+no_connect"))
    )
    (net (code "114") (name "unconnected-(U1B-TEST_GPIO[58]_1-PadAB3)") (class "Default")
      (node (ref "U1") (pin "AB3") (pinfunction "TEST_GPIO[58]_1_AB3") (pintype "passive+no_connect"))
    )
    (net (code "115") (name "unconnected-(U1B-TEST_GPIO[59]_1-PadAB4)") (class "Default")
      (node (ref "U1") (pin "AB4") (pinfunction "TEST_GPIO[59]_1_AB4") (pintype "passive+no_connect"))
    )
    (net (code "116") (name "unconnected-(U1B-TEST_GPIO[60]_1-PadAB2)") (class "Default")
      (node (ref "U1") (pin "AB2") (pinfunction "TEST_GPIO[60]_1_AB2") (pintype "passive+no_connect"))
    )
    (net (code "117") (name "unconnected-(U1B-TEST_GPIO[61]_1-PadAA1)") (class "Default")
      (node (ref "U1") (pin "AA1") (pinfunction "TEST_GPIO[61]_1_AA1") (pintype "passive+no_connect"))
    )
    (net (code "118") (name "unconnected-(U1B-TEST_GPIO[62]_1-PadAB1)") (class "Default")
      (node (ref "U1") (pin "AB1") (pinfunction "TEST_GPIO[62]_1_AB1") (pintype "passive+no_connect"))
    )
    (net (code "119") (name "unconnected-(U1B-TEST_GPIO[63]_1-PadAA2)") (class "Default")
      (node (ref "U1") (pin "AA2") (pinfunction "TEST_GPIO[63]_1_AA2") (pintype "passive+no_connect"))
    )
    (net (code "120") (name "unconnected-(U1B-TEST_GPIO[64]_1-PadAA4)") (class "Default")
      (node (ref "U1") (pin "AA4") (pinfunction "TEST_GPIO[64]_1_AA4") (pintype "passive+no_connect"))
    )
    (net (code "121") (name "unconnected-(U1B-TEST_GPIO[65]_1-PadY3)") (class "Default")
      (node (ref "U1") (pin "Y3") (pinfunction "TEST_GPIO[65]_1_Y3") (pintype "passive+no_connect"))
    )
    (net (code "122") (name "unconnected-(U1B-TEST_GPIO[66]_1-PadY2)") (class "Default")
      (node (ref "U1") (pin "Y2") (pinfunction "TEST_GPIO[66]_1_Y2") (pintype "passive+no_connect"))
    )
    (net (code "123") (name "unconnected-(U1B-TEST_GPIO[67]_1-PadY4)") (class "Default")
      (node (ref "U1") (pin "Y4") (pinfunction "TEST_GPIO[67]_1_Y4") (pintype "passive+no_connect"))
    )
    (net (code "124") (name "unconnected-(U1B-TEST_GPIO[68]_1-PadW1)") (class "Default")
      (node (ref "U1") (pin "W1") (pinfunction "TEST_GPIO[68]_1_W1") (pintype "passive+no_connect"))
    )
    (net (code "125") (name "unconnected-(U1B-TEST_GPIO[69]_1-PadW3)") (class "Default")
      (node (ref "U1") (pin "W3") (pinfunction "TEST_GPIO[69]_1_W3") (pintype "passive+no_connect"))
    )
    (net (code "126") (name "unconnected-(U1B-TEST_GPIO[70]_1-PadW2)") (class "Default")
      (node (ref "U1") (pin "W2") (pinfunction "TEST_GPIO[70]_1_W2") (pintype "passive+no_connect"))
    )
    (net (code "127") (name "unconnected-(U1B-TEST_GPIO[71]_1-PadW5)") (class "Default")
      (node (ref "U1") (pin "W5") (pinfunction "TEST_GPIO[71]_1_W5") (pintype "passive+no_connect"))
    )
    (net (code "128") (name "unconnected-(U1C-DBG_SPARE[0]_2-PadAP25)") (class "Default")
      (node (ref "U1") (pin "AP25") (pinfunction "DBG_SPARE[0]_2_AP25") (pintype "passive+no_connect"))
    )
    (net (code "129") (name "unconnected-(U1C-DBG_SPARE[1]_2-PadAR25)") (class "Default")
      (node (ref "U1") (pin "AR25") (pinfunction "DBG_SPARE[1]_2_AR25") (pintype "passive+no_connect"))
    )
    (net (code "130") (name "unconnected-(U1C-JTG_TCK_2-PadAF33)") (class "Default")
      (node (ref "U1") (pin "AF33") (pinfunction "JTG_TCK_2_AF33") (pintype "passive+no_connect"))
    )
    (net (code "131") (name "unconnected-(U1C-JTG_TDI_2-PadAF36)") (class "Default")
      (node (ref "U1") (pin "AF36") (pinfunction "JTG_TDI_2_AF36") (pintype "passive+no_connect"))
    )
    (net (code "132") (name "unconnected-(U1C-JTG_TDO_2-PadAE34)") (class "Default")
      (node (ref "U1") (pin "AE34") (pinfunction "JTG_TDO_2_AE34") (pintype "passive+no_connect"))
    )
    (net (code "133") (name "unconnected-(U1C-JTG_TMS_2-PadAE36)") (class "Default")
      (node (ref "U1") (pin "AE36") (pinfunction "JTG_TMS_2_AE36") (pintype "passive+no_connect"))
    )
    (net (code "134") (name "unconnected-(U1C-TEST_GPIO[0]_2-PadW35)") (class "Default")
      (node (ref "U1") (pin "W35") (pinfunction "TEST_GPIO[0]_2_W35") (pintype "passive+no_connect"))
    )
    (net (code "135") (name "unconnected-(U1C-TEST_GPIO[1]_2-PadY35)") (class "Default")
      (node (ref "U1") (pin "Y35") (pinfunction "TEST_GPIO[1]_2_Y35") (pintype "passive+no_connect"))
    )
    (net (code "136") (name "unconnected-(U1C-TEST_GPIO[2]_2-PadY34)") (class "Default")
      (node (ref "U1") (pin "Y34") (pinfunction "TEST_GPIO[2]_2_Y34") (pintype "passive+no_connect"))
    )
    (net (code "137") (name "unconnected-(U1C-TEST_GPIO[3]_2-PadY36)") (class "Default")
      (node (ref "U1") (pin "Y36") (pinfunction "TEST_GPIO[3]_2_Y36") (pintype "passive+no_connect"))
    )
    (net (code "138") (name "unconnected-(U1C-TEST_GPIO[4]_2-PadAA33)") (class "Default")
      (node (ref "U1") (pin "AA33") (pinfunction "TEST_GPIO[4]_2_AA33") (pintype "passive+no_connect"))
    )
    (net (code "139") (name "unconnected-(U1C-TEST_GPIO[5]_2-PadAA36)") (class "Default")
      (node (ref "U1") (pin "AA36") (pinfunction "TEST_GPIO[5]_2_AA36") (pintype "passive+no_connect"))
    )
    (net (code "140") (name "unconnected-(U1C-TEST_GPIO[6]_2-PadAA34)") (class "Default")
      (node (ref "U1") (pin "AA34") (pinfunction "TEST_GPIO[6]_2_AA34") (pintype "passive+no_connect"))
    )
    (net (code "141") (name "unconnected-(U1C-TEST_GPIO[7]_2-PadAB33)") (class "Default")
      (node (ref "U1") (pin "AB33") (pinfunction "TEST_GPIO[7]_2_AB33") (pintype "passive+no_connect"))
    )
    (net (code "142") (name "unconnected-(U1C-TEST_GPIO[8]_2-PadAB34)") (class "Default")
      (node (ref "U1") (pin "AB34") (pinfunction "TEST_GPIO[8]_2_AB34") (pintype "passive+no_connect"))
    )
    (net (code "143") (name "unconnected-(U1C-TEST_GPIO[9]_2-PadAB36)") (class "Default")
      (node (ref "U1") (pin "AB36") (pinfunction "TEST_GPIO[9]_2_AB36") (pintype "passive+no_connect"))
    )
    (net (code "144") (name "unconnected-(U1C-TEST_GPIO[10]_2-PadAB35)") (class "Default")
      (node (ref "U1") (pin "AB35") (pinfunction "TEST_GPIO[10]_2_AB35") (pintype "passive+no_connect"))
    )
    (net (code "145") (name "unconnected-(U1C-TEST_GPIO[11]_2-PadAC33)") (class "Default")
      (node (ref "U1") (pin "AC33") (pinfunction "TEST_GPIO[11]_2_AC33") (pintype "passive+no_connect"))
    )
    (net (code "146") (name "unconnected-(U1C-TEST_GPIO[12]_2-PadAC35)") (class "Default")
      (node (ref "U1") (pin "AC35") (pinfunction "TEST_GPIO[12]_2_AC35") (pintype "passive+no_connect"))
    )
    (net (code "147") (name "unconnected-(U1C-TEST_GPIO[13]_2-PadAD35)") (class "Default")
      (node (ref "U1") (pin "AD35") (pinfunction "TEST_GPIO[13]_2_AD35") (pintype "passive+no_connect"))
    )
    (net (code "148") (name "unconnected-(U1C-TEST_GPIO[14]_2-PadAC36)") (class "Default")
      (node (ref "U1") (pin "AC36") (pinfunction "TEST_GPIO[14]_2_AC36") (pintype "passive+no_connect"))
    )
    (net (code "149") (name "unconnected-(U1C-TEST_GPIO[15]_2-PadAD34)") (class "Default")
      (node (ref "U1") (pin "AD34") (pinfunction "TEST_GPIO[15]_2_AD34") (pintype "passive+no_connect"))
    )
    (net (code "150") (name "unconnected-(U1C-TEST_GPIO[16]_2-PadAF34)") (class "Default")
      (node (ref "U1") (pin "AF34") (pinfunction "TEST_GPIO[16]_2_AF34") (pintype "passive+no_connect"))
    )
    (net (code "151") (name "unconnected-(U1C-TEST_GPIO[17]_2-PadAG36)") (class "Default")
      (node (ref "U1") (pin "AG36") (pinfunction "TEST_GPIO[17]_2_AG36") (pintype "passive+no_connect"))
    )
    (net (code "152") (name "unconnected-(U1C-TEST_GPIO[18]_2-PadAG35)") (class "Default")
      (node (ref "U1") (pin "AG35") (pinfunction "TEST_GPIO[18]_2_AG35") (pintype "passive+no_connect"))
    )
    (net (code "153") (name "unconnected-(U1C-TEST_GPIO[19]_2-PadAG33)") (class "Default")
      (node (ref "U1") (pin "AG33") (pinfunction "TEST_GPIO[19]_2_AG33") (pintype "passive+no_connect"))
    )
    (net (code "154") (name "unconnected-(U1C-TEST_GPIO[20]_2-PadAG34)") (class "Default")
      (node (ref "U1") (pin "AG34") (pinfunction "TEST_GPIO[20]_2_AG34") (pintype "passive+no_connect"))
    )
    (net (code "155") (name "unconnected-(U1C-TEST_GPIO[21]_2-PadAH36)") (class "Default")
      (node (ref "U1") (pin "AH36") (pinfunction "TEST_GPIO[21]_2_AH36") (pintype "passive+no_connect"))
    )
    (net (code "156") (name "unconnected-(U1C-TEST_GPIO[22]_2-PadAH35)") (class "Default")
      (node (ref "U1") (pin "AH35") (pinfunction "TEST_GPIO[22]_2_AH35") (pintype "passive+no_connect"))
    )
    (net (code "157") (name "unconnected-(U1C-TEST_GPIO[23]_2-PadAJ35)") (class "Default")
      (node (ref "U1") (pin "AJ35") (pinfunction "TEST_GPIO[23]_2_AJ35") (pintype "passive+no_connect"))
    )
    (net (code "158") (name "unconnected-(U1C-TEST_GPIO[24]_2-PadAH33)") (class "Default")
      (node (ref "U1") (pin "AH33") (pinfunction "TEST_GPIO[24]_2_AH33") (pintype "passive+no_connect"))
    )
    (net (code "159") (name "unconnected-(U1C-TEST_GPIO[25]_2-PadAJ34)") (class "Default")
      (node (ref "U1") (pin "AJ34") (pinfunction "TEST_GPIO[25]_2_AJ34") (pintype "passive+no_connect"))
    )
    (net (code "160") (name "unconnected-(U1C-TEST_GPIO[26]_2-PadAJ33)") (class "Default")
      (node (ref "U1") (pin "AJ33") (pinfunction "TEST_GPIO[26]_2_AJ33") (pintype "passive+no_connect"))
    )
    (net (code "161") (name "unconnected-(U1C-TEST_GPIO[27]_2-PadAK35)") (class "Default")
      (node (ref "U1") (pin "AK35") (pinfunction "TEST_GPIO[27]_2_AK35") (pintype "passive+no_connect"))
    )
    (net (code "162") (name "unconnected-(U1C-TEST_GPIO[28]_2-PadAK36)") (class "Default")
      (node (ref "U1") (pin "AK36") (pinfunction "TEST_GPIO[28]_2_AK36") (pintype "passive+no_connect"))
    )
    (net (code "163") (name "unconnected-(U1C-TEST_GPIO[29]_2-PadAK34)") (class "Default")
      (node (ref "U1") (pin "AK34") (pinfunction "TEST_GPIO[29]_2_AK34") (pintype "passive+no_connect"))
    )
    (net (code "164") (name "unconnected-(U1C-TEST_GPIO[30]_2-PadAL36)") (class "Default")
      (node (ref "U1") (pin "AL36") (pinfunction "TEST_GPIO[30]_2_AL36") (pintype "passive+no_connect"))
    )
    (net (code "165") (name "unconnected-(U1C-TEST_GPIO[31]_2-PadAM36)") (class "Default")
      (node (ref "U1") (pin "AM36") (pinfunction "TEST_GPIO[31]_2_AM36") (pintype "passive+no_connect"))
    )
    (net (code "166") (name "unconnected-(U1C-TEST_GPIO[32]_2-PadAL34)") (class "Default")
      (node (ref "U1") (pin "AL34") (pinfunction "TEST_GPIO[32]_2_AL34") (pintype "passive+no_connect"))
    )
    (net (code "167") (name "unconnected-(U1C-TEST_GPIO[33]_2-PadAL33)") (class "Default")
      (node (ref "U1") (pin "AL33") (pinfunction "TEST_GPIO[33]_2_AL33") (pintype "passive+no_connect"))
    )
    (net (code "168") (name "unconnected-(U1C-TEST_GPIO[34]_2-PadAM33)") (class "Default")
      (node (ref "U1") (pin "AM33") (pinfunction "TEST_GPIO[34]_2_AM33") (pintype "passive+no_connect"))
    )
    (net (code "169") (name "unconnected-(U1C-TEST_GPIO[35]_2-PadAN36)") (class "Default")
      (node (ref "U1") (pin "AN36") (pinfunction "TEST_GPIO[35]_2_AN36") (pintype "passive+no_connect"))
    )
    (net (code "170") (name "unconnected-(U1C-TEST_GPIO[36]_2-PadAN35)") (class "Default")
      (node (ref "U1") (pin "AN35") (pinfunction "TEST_GPIO[36]_2_AN35") (pintype "passive+no_connect"))
    )
    (net (code "171") (name "unconnected-(U1C-TEST_GPIO[37]_2-PadAN33)") (class "Default")
      (node (ref "U1") (pin "AN33") (pinfunction "TEST_GPIO[37]_2_AN33") (pintype "passive+no_connect"))
    )
    (net (code "172") (name "unconnected-(U1C-TEST_GPIO[38]_2-PadAP35)") (class "Default")
      (node (ref "U1") (pin "AP35") (pinfunction "TEST_GPIO[38]_2_AP35") (pintype "passive+no_connect"))
    )
    (net (code "173") (name "unconnected-(U1C-TEST_GPIO[39]_2-PadAN32)") (class "Default")
      (node (ref "U1") (pin "AN32") (pinfunction "TEST_GPIO[39]_2_AN32") (pintype "passive+no_connect"))
    )
    (net (code "174") (name "unconnected-(U1C-TEST_GPIO[40]_2-PadAP34)") (class "Default")
      (node (ref "U1") (pin "AP34") (pinfunction "TEST_GPIO[40]_2_AP34") (pintype "passive+no_connect"))
    )
    (net (code "175") (name "unconnected-(U1C-TEST_GPIO[41]_2-PadAP33)") (class "Default")
      (node (ref "U1") (pin "AP33") (pinfunction "TEST_GPIO[41]_2_AP33") (pintype "passive+no_connect"))
    )
    (net (code "176") (name "unconnected-(U1C-TEST_GPIO[42]_2-PadAR35)") (class "Default")
      (node (ref "U1") (pin "AR35") (pinfunction "TEST_GPIO[42]_2_AR35") (pintype "passive+no_connect"))
    )
    (net (code "177") (name "unconnected-(U1C-TEST_GPIO[43]_2-PadAN31)") (class "Default")
      (node (ref "U1") (pin "AN31") (pinfunction "TEST_GPIO[43]_2_AN31") (pintype "passive+no_connect"))
    )
    (net (code "178") (name "unconnected-(U1C-TEST_GPIO[44]_2-PadAP32)") (class "Default")
      (node (ref "U1") (pin "AP32") (pinfunction "TEST_GPIO[44]_2_AP32") (pintype "passive+no_connect"))
    )
    (net (code "179") (name "unconnected-(U1C-TEST_GPIO[45]_2-PadAR34)") (class "Default")
      (node (ref "U1") (pin "AR34") (pinfunction "TEST_GPIO[45]_2_AR34") (pintype "passive+no_connect"))
    )
    (net (code "180") (name "unconnected-(U1C-TEST_GPIO[46]_2-PadAT34)") (class "Default")
      (node (ref "U1") (pin "AT34") (pinfunction "TEST_GPIO[46]_2_AT34") (pintype "passive+no_connect"))
    )
    (net (code "181") (name "unconnected-(U1C-TEST_GPIO[47]_2-PadAN30)") (class "Default")
      (node (ref "U1") (pin "AN30") (pinfunction "TEST_GPIO[47]_2_AN30") (pintype "passive+no_connect"))
    )
    (net (code "182") (name "unconnected-(U1C-TEST_GPIO[48]_2-PadAR32)") (class "Default")
      (node (ref "U1") (pin "AR32") (pinfunction "TEST_GPIO[48]_2_AR32") (pintype "passive+no_connect"))
    )
    (net (code "183") (name "unconnected-(U1C-TEST_GPIO[49]_2-PadAT33)") (class "Default")
      (node (ref "U1") (pin "AT33") (pinfunction "TEST_GPIO[49]_2_AT33") (pintype "passive+no_connect"))
    )
    (net (code "184") (name "unconnected-(U1C-TEST_GPIO[50]_2-PadAP30)") (class "Default")
      (node (ref "U1") (pin "AP30") (pinfunction "TEST_GPIO[50]_2_AP30") (pintype "passive+no_connect"))
    )
    (net (code "185") (name "unconnected-(U1C-TEST_GPIO[51]_2-PadAR31)") (class "Default")
      (node (ref "U1") (pin "AR31") (pinfunction "TEST_GPIO[51]_2_AR31") (pintype "passive+no_connect"))
    )
    (net (code "186") (name "unconnected-(U1C-TEST_GPIO[52]_2-PadAP24)") (class "Default")
      (node (ref "U1") (pin "AP24") (pinfunction "TEST_GPIO[52]_2_AP24") (pintype "passive+no_connect"))
    )
    (net (code "187") (name "unconnected-(U1C-TEST_GPIO[53]_2-PadAR24)") (class "Default")
      (node (ref "U1") (pin "AR24") (pinfunction "TEST_GPIO[53]_2_AR24") (pintype "passive+no_connect"))
    )
    (net (code "188") (name "unconnected-(U1C-TEST_GPIO[54]_2-PadAP23)") (class "Default")
      (node (ref "U1") (pin "AP23") (pinfunction "TEST_GPIO[54]_2_AP23") (pintype "passive+no_connect"))
    )
    (net (code "189") (name "unconnected-(U1C-TEST_GPIO[55]_2-PadAN23)") (class "Default")
      (node (ref "U1") (pin "AN23") (pinfunction "TEST_GPIO[55]_2_AN23") (pintype "passive+no_connect"))
    )
    (net (code "190") (name "unconnected-(U1C-TEST_GPIO[56]_2-PadAT24)") (class "Default")
      (node (ref "U1") (pin "AT24") (pinfunction "TEST_GPIO[56]_2_AT24") (pintype "passive+no_connect"))
    )
    (net (code "191") (name "unconnected-(U1C-TEST_GPIO[57]_2-PadAT23)") (class "Default")
      (node (ref "U1") (pin "AT23") (pinfunction "TEST_GPIO[57]_2_AT23") (pintype "passive+no_connect"))
    )
    (net (code "192") (name "unconnected-(U1C-TEST_GPIO[58]_2-PadAP22)") (class "Default")
      (node (ref "U1") (pin "AP22") (pinfunction "TEST_GPIO[58]_2_AP22") (pintype "passive+no_connect"))
    )
    (net (code "193") (name "unconnected-(U1C-TEST_GPIO[59]_2-PadAN22)") (class "Default")
      (node (ref "U1") (pin "AN22") (pinfunction "TEST_GPIO[59]_2_AN22") (pintype "passive+no_connect"))
    )
    (net (code "194") (name "unconnected-(U1C-TEST_GPIO[60]_2-PadAR22)") (class "Default")
      (node (ref "U1") (pin "AR22") (pinfunction "TEST_GPIO[60]_2_AR22") (pintype "passive+no_connect"))
    )
    (net (code "195") (name "unconnected-(U1C-TEST_GPIO[61]_2-PadAT21)") (class "Default")
      (node (ref "U1") (pin "AT21") (pinfunction "TEST_GPIO[61]_2_AT21") (pintype "passive+no_connect"))
    )
    (net (code "196") (name "unconnected-(U1C-TEST_GPIO[62]_2-PadAT22)") (class "Default")
      (node (ref "U1") (pin "AT22") (pinfunction "TEST_GPIO[62]_2_AT22") (pintype "passive+no_connect"))
    )
    (net (code "197") (name "unconnected-(U1C-TEST_GPIO[63]_2-PadAR21)") (class "Default")
      (node (ref "U1") (pin "AR21") (pinfunction "TEST_GPIO[63]_2_AR21") (pintype "passive+no_connect"))
    )
    (net (code "198") (name "unconnected-(U1C-TEST_GPIO[64]_2-PadAN21)") (class "Default")
      (node (ref "U1") (pin "AN21") (pinfunction "TEST_GPIO[64]_2_AN21") (pintype "passive+no_connect"))
    )
    (net (code "199") (name "unconnected-(U1C-TEST_GPIO[65]_2-PadAP20)") (class "Default")
      (node (ref "U1") (pin "AP20") (pinfunction "TEST_GPIO[65]_2_AP20") (pintype "passive+no_connect"))
    )
    (net (code "200") (name "unconnected-(U1C-TEST_GPIO[66]_2-PadAR20)") (class "Default")
      (node (ref "U1") (pin "AR20") (pinfunction "TEST_GPIO[66]_2_AR20") (pintype "passive+no_connect"))
    )
    (net (code "201") (name "unconnected-(U1C-TEST_GPIO[67]_2-PadAN20)") (class "Default")
      (node (ref "U1") (pin "AN20") (pinfunction "TEST_GPIO[67]_2_AN20") (pintype "passive+no_connect"))
    )
    (net (code "202") (name "unconnected-(U1C-TEST_GPIO[68]_2-PadAT19)") (class "Default")
      (node (ref "U1") (pin "AT19") (pinfunction "TEST_GPIO[68]_2_AT19") (pintype "passive+no_connect"))
    )
    (net (code "203") (name "unconnected-(U1C-TEST_GPIO[69]_2-PadAP19)") (class "Default")
      (node (ref "U1") (pin "AP19") (pinfunction "TEST_GPIO[69]_2_AP19") (pintype "passive+no_connect"))
    )
    (net (code "204") (name "unconnected-(U1C-TEST_GPIO[70]_2-PadAR19)") (class "Default")
      (node (ref "U1") (pin "AR19") (pinfunction "TEST_GPIO[70]_2_AR19") (pintype "passive+no_connect"))
    )
    (net (code "205") (name "unconnected-(U1C-TEST_GPIO[71]_2-PadAM19)") (class "Default")
      (node (ref "U1") (pin "AM19") (pinfunction "TEST_GPIO[71]_2_AM19") (pintype "passive+no_connect"))
    )
    (net (code "206") (name "unconnected-(U1D-DBG_SPARE[0]_3-PadM34)") (class "Default")
      (node (ref "U1") (pin "M34") (pinfunction "DBG_SPARE[0]_3_M34") (pintype "passive+no_connect"))
    )
    (net (code "207") (name "unconnected-(U1D-DBG_SPARE[1]_3-PadM35)") (class "Default")
      (node (ref "U1") (pin "M35") (pinfunction "DBG_SPARE[1]_3_M35") (pintype "passive+no_connect"))
    )
    (net (code "208") (name "unconnected-(U1D-JTG_TCK_3-PadD26)") (class "Default")
      (node (ref "U1") (pin "D26") (pinfunction "JTG_TCK_3_D26") (pintype "passive+no_connect"))
    )
    (net (code "209") (name "unconnected-(U1D-JTG_TDI_3-PadA26)") (class "Default")
      (node (ref "U1") (pin "A26") (pinfunction "JTG_TDI_3_A26") (pintype "passive+no_connect"))
    )
    (net (code "210") (name "unconnected-(U1D-JTG_TDO_3-PadC25)") (class "Default")
      (node (ref "U1") (pin "C25") (pinfunction "JTG_TDO_3_C25") (pintype "passive+no_connect"))
    )
    (net (code "211") (name "unconnected-(U1D-JTG_TMS_3-PadA25)") (class "Default")
      (node (ref "U1") (pin "A25") (pinfunction "JTG_TMS_3_A25") (pintype "passive+no_connect"))
    )
    (net (code "212") (name "unconnected-(U1D-TEST_GPIO[0]_3-PadB19)") (class "Default")
      (node (ref "U1") (pin "B19") (pinfunction "TEST_GPIO[0]_3_B19") (pintype "passive+no_connect"))
    )
    (net (code "213") (name "unconnected-(U1D-TEST_GPIO[1]_3-PadB20)") (class "Default")
      (node (ref "U1") (pin "B20") (pinfunction "TEST_GPIO[1]_3_B20") (pintype "passive+no_connect"))
    )
    (net (code "214") (name "unconnected-(U1D-TEST_GPIO[2]_3-PadC20)") (class "Default")
      (node (ref "U1") (pin "C20") (pinfunction "TEST_GPIO[2]_3_C20") (pintype "passive+no_connect"))
    )
    (net (code "215") (name "unconnected-(U1D-TEST_GPIO[3]_3-PadA20)") (class "Default")
      (node (ref "U1") (pin "A20") (pinfunction "TEST_GPIO[3]_3_A20") (pintype "passive+no_connect"))
    )
    (net (code "216") (name "unconnected-(U1D-TEST_GPIO[4]_3-PadD21)") (class "Default")
      (node (ref "U1") (pin "D21") (pinfunction "TEST_GPIO[4]_3_D21") (pintype "passive+no_connect"))
    )
    (net (code "217") (name "unconnected-(U1D-TEST_GPIO[5]_3-PadA21)") (class "Default")
      (node (ref "U1") (pin "A21") (pinfunction "TEST_GPIO[5]_3_A21") (pintype "passive+no_connect"))
    )
    (net (code "218") (name "unconnected-(U1D-TEST_GPIO[6]_3-PadC21)") (class "Default")
      (node (ref "U1") (pin "C21") (pinfunction "TEST_GPIO[6]_3_C21") (pintype "passive+no_connect"))
    )
    (net (code "219") (name "unconnected-(U1D-TEST_GPIO[7]_3-PadD22)") (class "Default")
      (node (ref "U1") (pin "D22") (pinfunction "TEST_GPIO[7]_3_D22") (pintype "passive+no_connect"))
    )
    (net (code "220") (name "unconnected-(U1D-TEST_GPIO[8]_3-PadC22)") (class "Default")
      (node (ref "U1") (pin "C22") (pinfunction "TEST_GPIO[8]_3_C22") (pintype "passive+no_connect"))
    )
    (net (code "221") (name "unconnected-(U1D-TEST_GPIO[9]_3-PadA22)") (class "Default")
      (node (ref "U1") (pin "A22") (pinfunction "TEST_GPIO[9]_3_A22") (pintype "passive+no_connect"))
    )
    (net (code "222") (name "unconnected-(U1D-TEST_GPIO[10]_3-PadB22)") (class "Default")
      (node (ref "U1") (pin "B22") (pinfunction "TEST_GPIO[10]_3_B22") (pintype "passive+no_connect"))
    )
    (net (code "223") (name "unconnected-(U1D-TEST_GPIO[11]_3-PadD23)") (class "Default")
      (node (ref "U1") (pin "D23") (pinfunction "TEST_GPIO[11]_3_D23") (pintype "passive+no_connect"))
    )
    (net (code "224") (name "unconnected-(U1D-TEST_GPIO[12]_3-PadB23)") (class "Default")
      (node (ref "U1") (pin "B23") (pinfunction "TEST_GPIO[12]_3_B23") (pintype "passive+no_connect"))
    )
    (net (code "225") (name "unconnected-(U1D-TEST_GPIO[13]_3-PadB24)") (class "Default")
      (node (ref "U1") (pin "B24") (pinfunction "TEST_GPIO[13]_3_B24") (pintype "passive+no_connect"))
    )
    (net (code "226") (name "unconnected-(U1D-TEST_GPIO[14]_3-PadA23)") (class "Default")
      (node (ref "U1") (pin "A23") (pinfunction "TEST_GPIO[14]_3_A23") (pintype "passive+no_connect"))
    )
    (net (code "227") (name "unconnected-(U1D-TEST_GPIO[15]_3-PadC24)") (class "Default")
      (node (ref "U1") (pin "C24") (pinfunction "TEST_GPIO[15]_3_C24") (pintype "passive+no_connect"))
    )
    (net (code "228") (name "unconnected-(U1D-TEST_GPIO[16]_3-PadC26)") (class "Default")
      (node (ref "U1") (pin "C26") (pinfunction "TEST_GPIO[16]_3_C26") (pintype "passive+no_connect"))
    )
    (net (code "229") (name "unconnected-(U1D-TEST_GPIO[17]_3-PadA27)") (class "Default")
      (node (ref "U1") (pin "A27") (pinfunction "TEST_GPIO[17]_3_A27") (pintype "passive+no_connect"))
    )
    (net (code "230") (name "unconnected-(U1D-TEST_GPIO[18]_3-PadB27)") (class "Default")
      (node (ref "U1") (pin "B27") (pinfunction "TEST_GPIO[18]_3_B27") (pintype "passive+no_connect"))
    )
    (net (code "231") (name "unconnected-(U1D-TEST_GPIO[19]_3-PadD27)") (class "Default")
      (node (ref "U1") (pin "D27") (pinfunction "TEST_GPIO[19]_3_D27") (pintype "passive+no_connect"))
    )
    (net (code "232") (name "unconnected-(U1D-TEST_GPIO[20]_3-PadC27)") (class "Default")
      (node (ref "U1") (pin "C27") (pinfunction "TEST_GPIO[20]_3_C27") (pintype "passive+no_connect"))
    )
    (net (code "233") (name "unconnected-(U1D-TEST_GPIO[21]_3-PadA28)") (class "Default")
      (node (ref "U1") (pin "A28") (pinfunction "TEST_GPIO[21]_3_A28") (pintype "passive+no_connect"))
    )
    (net (code "234") (name "unconnected-(U1D-TEST_GPIO[22]_3-PadB28)") (class "Default")
      (node (ref "U1") (pin "B28") (pinfunction "TEST_GPIO[22]_3_B28") (pintype "passive+no_connect"))
    )
    (net (code "235") (name "unconnected-(U1D-TEST_GPIO[23]_3-PadB29)") (class "Default")
      (node (ref "U1") (pin "B29") (pinfunction "TEST_GPIO[23]_3_B29") (pintype "passive+no_connect"))
    )
    (net (code "236") (name "unconnected-(U1D-TEST_GPIO[24]_3-PadD28)") (class "Default")
      (node (ref "U1") (pin "D28") (pinfunction "TEST_GPIO[24]_3_D28") (pintype "passive+no_connect"))
    )
    (net (code "237") (name "unconnected-(U1D-TEST_GPIO[25]_3-PadC29)") (class "Default")
      (node (ref "U1") (pin "C29") (pinfunction "TEST_GPIO[25]_3_C29") (pintype "passive+no_connect"))
    )
    (net (code "238") (name "unconnected-(U1D-TEST_GPIO[26]_3-PadD29)") (class "Default")
      (node (ref "U1") (pin "D29") (pinfunction "TEST_GPIO[26]_3_D29") (pintype "passive+no_connect"))
    )
    (net (code "239") (name "unconnected-(U1D-TEST_GPIO[27]_3-PadB30)") (class "Default")
      (node (ref "U1") (pin "B30") (pinfunction "TEST_GPIO[27]_3_B30") (pintype "passive+no_connect"))
    )
    (net (code "240") (name "unconnected-(U1D-TEST_GPIO[28]_3-PadA30)") (class "Default")
      (node (ref "U1") (pin "A30") (pinfunction "TEST_GPIO[28]_3_A30") (pintype "passive+no_connect"))
    )
    (net (code "241") (name "unconnected-(U1D-TEST_GPIO[29]_3-PadC30)") (class "Default")
      (node (ref "U1") (pin "C30") (pinfunction "TEST_GPIO[29]_3_C30") (pintype "passive+no_connect"))
    )
    (net (code "242") (name "unconnected-(U1D-TEST_GPIO[30]_3-PadA31)") (class "Default")
      (node (ref "U1") (pin "A31") (pinfunction "TEST_GPIO[30]_3_A31") (pintype "passive+no_connect"))
    )
    (net (code "243") (name "unconnected-(U1D-TEST_GPIO[31]_3-PadA32)") (class "Default")
      (node (ref "U1") (pin "A32") (pinfunction "TEST_GPIO[31]_3_A32") (pintype "passive+no_connect"))
    )
    (net (code "244") (name "unconnected-(U1D-TEST_GPIO[32]_3-PadC31)") (class "Default")
      (node (ref "U1") (pin "C31") (pinfunction "TEST_GPIO[32]_3_C31") (pintype "passive+no_connect"))
    )
    (net (code "245") (name "unconnected-(U1D-TEST_GPIO[33]_3-PadD31)") (class "Default")
      (node (ref "U1") (pin "D31") (pinfunction "TEST_GPIO[33]_3_D31") (pintype "passive+no_connect"))
    )
    (net (code "246") (name "unconnected-(U1D-TEST_GPIO[34]_3-PadD32)") (class "Default")
      (node (ref "U1") (pin "D32") (pinfunction "TEST_GPIO[34]_3_D32") (pintype "passive+no_connect"))
    )
    (net (code "247") (name "unconnected-(U1D-TEST_GPIO[35]_3-PadA33)") (class "Default")
      (node (ref "U1") (pin "A33") (pinfunction "TEST_GPIO[35]_3_A33") (pintype "passive+no_connect"))
    )
    (net (code "248") (name "unconnected-(U1D-TEST_GPIO[36]_3-PadB33)") (class "Default")
      (node (ref "U1") (pin "B33") (pinfunction "TEST_GPIO[36]_3_B33") (pintype "passive+no_connect"))
    )
    (net (code "249") (name "unconnected-(U1D-TEST_GPIO[37]_3-PadD33)") (class "Default")
      (node (ref "U1") (pin "D33") (pinfunction "TEST_GPIO[37]_3_D33") (pintype "passive+no_connect"))
    )
    (net (code "250") (name "unconnected-(U1D-TEST_GPIO[38]_3-PadB34)") (class "Default")
      (node (ref "U1") (pin "B34") (pinfunction "TEST_GPIO[38]_3_B34") (pintype "passive+no_connect"))
    )
    (net (code "251") (name "unconnected-(U1D-TEST_GPIO[39]_3-PadE33)") (class "Default")
      (node (ref "U1") (pin "E33") (pinfunction "TEST_GPIO[39]_3_E33") (pintype "passive+no_connect"))
    )
    (net (code "252") (name "unconnected-(U1D-TEST_GPIO[40]_3-PadC34)") (class "Default")
      (node (ref "U1") (pin "C34") (pinfunction "TEST_GPIO[40]_3_C34") (pintype "passive+no_connect"))
    )
    (net (code "253") (name "unconnected-(U1D-TEST_GPIO[41]_3-PadD34)") (class "Default")
      (node (ref "U1") (pin "D34") (pinfunction "TEST_GPIO[41]_3_D34") (pintype "passive+no_connect"))
    )
    (net (code "254") (name "unconnected-(U1D-TEST_GPIO[42]_3-PadB35)") (class "Default")
      (node (ref "U1") (pin "B35") (pinfunction "TEST_GPIO[42]_3_B35") (pintype "passive+no_connect"))
    )
    (net (code "255") (name "unconnected-(U1D-TEST_GPIO[43]_3-PadF33)") (class "Default")
      (node (ref "U1") (pin "F33") (pinfunction "TEST_GPIO[43]_3_F33") (pintype "passive+no_connect"))
    )
    (net (code "256") (name "unconnected-(U1D-TEST_GPIO[44]_3-PadE34)") (class "Default")
      (node (ref "U1") (pin "E34") (pinfunction "TEST_GPIO[44]_3_E34") (pintype "passive+no_connect"))
    )
    (net (code "257") (name "unconnected-(U1D-TEST_GPIO[45]_3-PadC35)") (class "Default")
      (node (ref "U1") (pin "C35") (pinfunction "TEST_GPIO[45]_3_C35") (pintype "passive+no_connect"))
    )
    (net (code "258") (name "unconnected-(U1D-TEST_GPIO[46]_3-PadC36)") (class "Default")
      (node (ref "U1") (pin "C36") (pinfunction "TEST_GPIO[46]_3_C36") (pintype "passive+no_connect"))
    )
    (net (code "259") (name "unconnected-(U1D-TEST_GPIO[47]_3-PadG33)") (class "Default")
      (node (ref "U1") (pin "G33") (pinfunction "TEST_GPIO[47]_3_G33") (pintype "passive+no_connect"))
    )
    (net (code "260") (name "unconnected-(U1D-TEST_GPIO[48]_3-PadE35)") (class "Default")
      (node (ref "U1") (pin "E35") (pinfunction "TEST_GPIO[48]_3_E35") (pintype "passive+no_connect"))
    )
    (net (code "261") (name "unconnected-(U1D-TEST_GPIO[49]_3-PadD36)") (class "Default")
      (node (ref "U1") (pin "D36") (pinfunction "TEST_GPIO[49]_3_D36") (pintype "passive+no_connect"))
    )
    (net (code "262") (name "unconnected-(U1D-TEST_GPIO[50]_3-PadG34)") (class "Default")
      (node (ref "U1") (pin "G34") (pinfunction "TEST_GPIO[50]_3_G34") (pintype "passive+no_connect"))
    )
    (net (code "263") (name "unconnected-(U1D-TEST_GPIO[51]_3-PadF35)") (class "Default")
      (node (ref "U1") (pin "F35") (pinfunction "TEST_GPIO[51]_3_F35") (pintype "passive+no_connect"))
    )
    (net (code "264") (name "unconnected-(U1D-TEST_GPIO[52]_3-PadN34)") (class "Default")
      (node (ref "U1") (pin "N34") (pinfunction "TEST_GPIO[52]_3_N34") (pintype "passive+no_connect"))
    )
    (net (code "265") (name "unconnected-(U1D-TEST_GPIO[53]_3-PadN35)") (class "Default")
      (node (ref "U1") (pin "N35") (pinfunction "TEST_GPIO[53]_3_N35") (pintype "passive+no_connect"))
    )
    (net (code "266") (name "unconnected-(U1D-TEST_GPIO[54]_3-PadP34)") (class "Default")
      (node (ref "U1") (pin "P34") (pinfunction "TEST_GPIO[54]_3_P34") (pintype "passive+no_connect"))
    )
    (net (code "267") (name "unconnected-(U1D-TEST_GPIO[55]_3-PadP33)") (class "Default")
      (node (ref "U1") (pin "P33") (pinfunction "TEST_GPIO[55]_3_P33") (pintype "passive+no_connect"))
    )
    (net (code "268") (name "unconnected-(U1D-TEST_GPIO[56]_3-PadN36)") (class "Default")
      (node (ref "U1") (pin "N36") (pinfunction "TEST_GPIO[56]_3_N36") (pintype "passive+no_connect"))
    )
    (net (code "269") (name "unconnected-(U1D-TEST_GPIO[57]_3-PadP36)") (class "Default")
      (node (ref "U1") (pin "P36") (pinfunction "TEST_GPIO[57]_3_P36") (pintype "passive+no_connect"))
    )
    (net (code "270") (name "unconnected-(U1D-TEST_GPIO[58]_3-PadR34)") (class "Default")
      (node (ref "U1") (pin "R34") (pinfunction "TEST_GPIO[58]_3_R34") (pintype "passive+no_connect"))
    )
    (net (code "271") (name "unconnected-(U1D-TEST_GPIO[59]_3-PadR33)") (class "Default")
      (node (ref "U1") (pin "R33") (pinfunction "TEST_GPIO[59]_3_R33") (pintype "passive+no_connect"))
    )
    (net (code "272") (name "unconnected-(U1D-TEST_GPIO[60]_3-PadR35)") (class "Default")
      (node (ref "U1") (pin "R35") (pinfunction "TEST_GPIO[60]_3_R35") (pintype "passive+no_connect"))
    )
    (net (code "273") (name "unconnected-(U1D-TEST_GPIO[61]_3-PadT36)") (class "Default")
      (node (ref "U1") (pin "T36") (pinfunction "TEST_GPIO[61]_3_T36") (pintype "passive+no_connect"))
    )
    (net (code "274") (name "unconnected-(U1D-TEST_GPIO[62]_3-PadR36)") (class "Default")
      (node (ref "U1") (pin "R36") (pinfunction "TEST_GPIO[62]_3_R36") (pintype "passive+no_connect"))
    )
    (net (code "275") (name "unconnected-(U1D-TEST_GPIO[63]_3-PadT35)") (class "Default")
      (node (ref "U1") (pin "T35") (pinfunction "TEST_GPIO[63]_3_T35") (pintype "passive+no_connect"))
    )
    (net (code "276") (name "unconnected-(U1D-TEST_GPIO[64]_3-PadT33)") (class "Default")
      (node (ref "U1") (pin "T33") (pinfunction "TEST_GPIO[64]_3_T33") (pintype "passive+no_connect"))
    )
    (net (code "277") (name "unconnected-(U1D-TEST_GPIO[65]_3-PadU34)") (class "Default")
      (node (ref "U1") (pin "U34") (pinfunction "TEST_GPIO[65]_3_U34") (pintype "passive+no_connect"))
    )
    (net (code "278") (name "unconnected-(U1D-TEST_GPIO[66]_3-PadU35)") (class "Default")
      (node (ref "U1") (pin "U35") (pinfunction "TEST_GPIO[66]_3_U35") (pintype "passive+no_connect"))
    )
    (net (code "279") (name "unconnected-(U1D-TEST_GPIO[67]_3-PadU33)") (class "Default")
      (node (ref "U1") (pin "U33") (pinfunction "TEST_GPIO[67]_3_U33") (pintype "passive+no_connect"))
    )
    (net (code "280") (name "unconnected-(U1D-TEST_GPIO[68]_3-PadV36)") (class "Default")
      (node (ref "U1") (pin "V36") (pinfunction "TEST_GPIO[68]_3_V36") (pintype "passive+no_connect"))
    )
    (net (code "281") (name "unconnected-(U1D-TEST_GPIO[69]_3-PadV34)") (class "Default")
      (node (ref "U1") (pin "V34") (pinfunction "TEST_GPIO[69]_3_V34") (pintype "passive+no_connect"))
    )
    (net (code "282") (name "unconnected-(U1D-TEST_GPIO[70]_3-PadV35)") (class "Default")
      (node (ref "U1") (pin "V35") (pinfunction "TEST_GPIO[70]_3_V35") (pintype "passive+no_connect"))
    )
    (net (code "283") (name "unconnected-(U1D-TEST_GPIO[71]_3-PadV32)") (class "Default")
      (node (ref "U1") (pin "V32") (pinfunction "TEST_GPIO[71]_3_V32") (pintype "passive+no_connect"))
    )
    (net (code "284") (name "unconnected-(U1E-DBG_SPARE[0]_4-PadC12)") (class "Default")
      (node (ref "U1") (pin "C12") (pinfunction "DBG_SPARE[0]_4_C12") (pintype "passive+no_connect"))
    )
    (net (code "285") (name "unconnected-(U1E-DBG_SPARE[1]_4-PadB12)") (class "Default")
      (node (ref "U1") (pin "B12") (pinfunction "DBG_SPARE[1]_4_B12") (pintype "passive+no_connect"))
    )
    (net (code "286") (name "unconnected-(U1E-JTG_TCK_4-PadL4)") (class "Default")
      (node (ref "U1") (pin "L4") (pinfunction "JTG_TCK_4_L4") (pintype "passive+no_connect"))
    )
    (net (code "287") (name "unconnected-(U1E-JTG_TDI_4-PadL1)") (class "Default")
      (node (ref "U1") (pin "L1") (pinfunction "JTG_TDI_4_L1") (pintype "passive+no_connect"))
    )
    (net (code "288") (name "unconnected-(U1E-JTG_TDO_4-PadM3)") (class "Default")
      (node (ref "U1") (pin "M3") (pinfunction "JTG_TDO_4_M3") (pintype "passive+no_connect"))
    )
    (net (code "289") (name "unconnected-(U1E-JTG_TMS_4-PadM1)") (class "Default")
      (node (ref "U1") (pin "M1") (pinfunction "JTG_TMS_4_M1") (pintype "passive+no_connect"))
    )
    (net (code "290") (name "unconnected-(U1E-TEST_GPIO[0]_4-PadV2)") (class "Default")
      (node (ref "U1") (pin "V2") (pinfunction "TEST_GPIO[0]_4_V2") (pintype "passive+no_connect"))
    )
    (net (code "291") (name "unconnected-(U1E-TEST_GPIO[1]_4-PadU2)") (class "Default")
      (node (ref "U1") (pin "U2") (pinfunction "TEST_GPIO[1]_4_U2") (pintype "passive+no_connect"))
    )
    (net (code "292") (name "unconnected-(U1E-TEST_GPIO[2]_4-PadU3)") (class "Default")
      (node (ref "U1") (pin "U3") (pinfunction "TEST_GPIO[2]_4_U3") (pintype "passive+no_connect"))
    )
    (net (code "293") (name "unconnected-(U1E-TEST_GPIO[3]_4-PadU1)") (class "Default")
      (node (ref "U1") (pin "U1") (pinfunction "TEST_GPIO[3]_4_U1") (pintype "passive+no_connect"))
    )
    (net (code "294") (name "unconnected-(U1E-TEST_GPIO[4]_4-PadT4)") (class "Default")
      (node (ref "U1") (pin "T4") (pinfunction "TEST_GPIO[4]_4_T4") (pintype "passive+no_connect"))
    )
    (net (code "295") (name "unconnected-(U1E-TEST_GPIO[5]_4-PadT1)") (class "Default")
      (node (ref "U1") (pin "T1") (pinfunction "TEST_GPIO[5]_4_T1") (pintype "passive+no_connect"))
    )
    (net (code "296") (name "unconnected-(U1E-TEST_GPIO[6]_4-PadT3)") (class "Default")
      (node (ref "U1") (pin "T3") (pinfunction "TEST_GPIO[6]_4_T3") (pintype "passive+no_connect"))
    )
    (net (code "297") (name "unconnected-(U1E-TEST_GPIO[7]_4-PadR4)") (class "Default")
      (node (ref "U1") (pin "R4") (pinfunction "TEST_GPIO[7]_4_R4") (pintype "passive+no_connect"))
    )
    (net (code "298") (name "unconnected-(U1E-TEST_GPIO[8]_4-PadR3)") (class "Default")
      (node (ref "U1") (pin "R3") (pinfunction "TEST_GPIO[8]_4_R3") (pintype "passive+no_connect"))
    )
    (net (code "299") (name "unconnected-(U1E-TEST_GPIO[9]_4-PadR1)") (class "Default")
      (node (ref "U1") (pin "R1") (pinfunction "TEST_GPIO[9]_4_R1") (pintype "passive+no_connect"))
    )
    (net (code "300") (name "unconnected-(U1E-TEST_GPIO[10]_4-PadR2)") (class "Default")
      (node (ref "U1") (pin "R2") (pinfunction "TEST_GPIO[10]_4_R2") (pintype "passive+no_connect"))
    )
    (net (code "301") (name "unconnected-(U1E-TEST_GPIO[11]_4-PadP4)") (class "Default")
      (node (ref "U1") (pin "P4") (pinfunction "TEST_GPIO[11]_4_P4") (pintype "passive+no_connect"))
    )
    (net (code "302") (name "unconnected-(U1E-TEST_GPIO[12]_4-PadP2)") (class "Default")
      (node (ref "U1") (pin "P2") (pinfunction "TEST_GPIO[12]_4_P2") (pintype "passive+no_connect"))
    )
    (net (code "303") (name "unconnected-(U1E-TEST_GPIO[13]_4-PadN2)") (class "Default")
      (node (ref "U1") (pin "N2") (pinfunction "TEST_GPIO[13]_4_N2") (pintype "passive+no_connect"))
    )
    (net (code "304") (name "unconnected-(U1E-TEST_GPIO[14]_4-PadP1)") (class "Default")
      (node (ref "U1") (pin "P1") (pinfunction "TEST_GPIO[14]_4_P1") (pintype "passive+no_connect"))
    )
    (net (code "305") (name "unconnected-(U1E-TEST_GPIO[15]_4-PadN3)") (class "Default")
      (node (ref "U1") (pin "N3") (pinfunction "TEST_GPIO[15]_4_N3") (pintype "passive+no_connect"))
    )
    (net (code "306") (name "unconnected-(U1E-TEST_GPIO[16]_4-PadL3)") (class "Default")
      (node (ref "U1") (pin "L3") (pinfunction "TEST_GPIO[16]_4_L3") (pintype "passive+no_connect"))
    )
    (net (code "307") (name "unconnected-(U1E-TEST_GPIO[17]_4-PadK1)") (class "Default")
      (node (ref "U1") (pin "K1") (pinfunction "TEST_GPIO[17]_4_K1") (pintype "passive+no_connect"))
    )
    (net (code "308") (name "unconnected-(U1E-TEST_GPIO[18]_4-PadK2)") (class "Default")
      (node (ref "U1") (pin "K2") (pinfunction "TEST_GPIO[18]_4_K2") (pintype "passive+no_connect"))
    )
    (net (code "309") (name "unconnected-(U1E-TEST_GPIO[19]_4-PadK4)") (class "Default")
      (node (ref "U1") (pin "K4") (pinfunction "TEST_GPIO[19]_4_K4") (pintype "passive+no_connect"))
    )
    (net (code "310") (name "unconnected-(U1E-TEST_GPIO[20]_4-PadK3)") (class "Default")
      (node (ref "U1") (pin "K3") (pinfunction "TEST_GPIO[20]_4_K3") (pintype "passive+no_connect"))
    )
    (net (code "311") (name "unconnected-(U1E-TEST_GPIO[21]_4-PadJ1)") (class "Default")
      (node (ref "U1") (pin "J1") (pinfunction "TEST_GPIO[21]_4_J1") (pintype "passive+no_connect"))
    )
    (net (code "312") (name "unconnected-(U1E-TEST_GPIO[22]_4-PadJ2)") (class "Default")
      (node (ref "U1") (pin "J2") (pinfunction "TEST_GPIO[22]_4_J2") (pintype "passive+no_connect"))
    )
    (net (code "313") (name "unconnected-(U1E-TEST_GPIO[23]_4-PadH2)") (class "Default")
      (node (ref "U1") (pin "H2") (pinfunction "TEST_GPIO[23]_4_H2") (pintype "passive+no_connect"))
    )
    (net (code "314") (name "unconnected-(U1E-TEST_GPIO[24]_4-PadJ4)") (class "Default")
      (node (ref "U1") (pin "J4") (pinfunction "TEST_GPIO[24]_4_J4") (pintype "passive+no_connect"))
    )
    (net (code "315") (name "unconnected-(U1E-TEST_GPIO[25]_4-PadH3)") (class "Default")
      (node (ref "U1") (pin "H3") (pinfunction "TEST_GPIO[25]_4_H3") (pintype "passive+no_connect"))
    )
    (net (code "316") (name "unconnected-(U1E-TEST_GPIO[26]_4-PadH4)") (class "Default")
      (node (ref "U1") (pin "H4") (pinfunction "TEST_GPIO[26]_4_H4") (pintype "passive+no_connect"))
    )
    (net (code "317") (name "unconnected-(U1E-TEST_GPIO[27]_4-PadG2)") (class "Default")
      (node (ref "U1") (pin "G2") (pinfunction "TEST_GPIO[27]_4_G2") (pintype "passive+no_connect"))
    )
    (net (code "318") (name "unconnected-(U1E-TEST_GPIO[28]_4-PadG1)") (class "Default")
      (node (ref "U1") (pin "G1") (pinfunction "TEST_GPIO[28]_4_G1") (pintype "passive+no_connect"))
    )
    (net (code "319") (name "unconnected-(U1E-TEST_GPIO[29]_4-PadG3)") (class "Default")
      (node (ref "U1") (pin "G3") (pinfunction "TEST_GPIO[29]_4_G3") (pintype "passive+no_connect"))
    )
    (net (code "320") (name "unconnected-(U1E-TEST_GPIO[30]_4-PadF1)") (class "Default")
      (node (ref "U1") (pin "F1") (pinfunction "TEST_GPIO[30]_4_F1") (pintype "passive+no_connect"))
    )
    (net (code "321") (name "unconnected-(U1E-TEST_GPIO[31]_4-PadE1)") (class "Default")
      (node (ref "U1") (pin "E1") (pinfunction "TEST_GPIO[31]_4_E1") (pintype "passive+no_connect"))
    )
    (net (code "322") (name "unconnected-(U1E-TEST_GPIO[32]_4-PadF3)") (class "Default")
      (node (ref "U1") (pin "F3") (pinfunction "TEST_GPIO[32]_4_F3") (pintype "passive+no_connect"))
    )
    (net (code "323") (name "unconnected-(U1E-TEST_GPIO[33]_4-PadF4)") (class "Default")
      (node (ref "U1") (pin "F4") (pinfunction "TEST_GPIO[33]_4_F4") (pintype "passive+no_connect"))
    )
    (net (code "324") (name "unconnected-(U1E-TEST_GPIO[34]_4-PadE4)") (class "Default")
      (node (ref "U1") (pin "E4") (pinfunction "TEST_GPIO[34]_4_E4") (pintype "passive+no_connect"))
    )
    (net (code "325") (name "unconnected-(U1E-TEST_GPIO[35]_4-PadD1)") (class "Default")
      (node (ref "U1") (pin "D1") (pinfunction "TEST_GPIO[35]_4_D1") (pintype "passive+no_connect"))
    )
    (net (code "326") (name "unconnected-(U1E-TEST_GPIO[36]_4-PadD2)") (class "Default")
      (node (ref "U1") (pin "D2") (pinfunction "TEST_GPIO[36]_4_D2") (pintype "passive+no_connect"))
    )
    (net (code "327") (name "unconnected-(U1E-TEST_GPIO[37]_4-PadD4)") (class "Default")
      (node (ref "U1") (pin "D4") (pinfunction "TEST_GPIO[37]_4_D4") (pintype "passive+no_connect"))
    )
    (net (code "328") (name "unconnected-(U1E-TEST_GPIO[38]_4-PadC2)") (class "Default")
      (node (ref "U1") (pin "C2") (pinfunction "TEST_GPIO[38]_4_C2") (pintype "passive+no_connect"))
    )
    (net (code "329") (name "unconnected-(U1E-TEST_GPIO[39]_4-PadD5)") (class "Default")
      (node (ref "U1") (pin "D5") (pinfunction "TEST_GPIO[39]_4_D5") (pintype "passive+no_connect"))
    )
    (net (code "330") (name "unconnected-(U1E-TEST_GPIO[40]_4-PadC3)") (class "Default")
      (node (ref "U1") (pin "C3") (pinfunction "TEST_GPIO[40]_4_C3") (pintype "passive+no_connect"))
    )
    (net (code "331") (name "unconnected-(U1E-TEST_GPIO[41]_4-PadC4)") (class "Default")
      (node (ref "U1") (pin "C4") (pinfunction "TEST_GPIO[41]_4_C4") (pintype "passive+no_connect"))
    )
    (net (code "332") (name "unconnected-(U1E-TEST_GPIO[42]_4-PadB2)") (class "Default")
      (node (ref "U1") (pin "B2") (pinfunction "TEST_GPIO[42]_4_B2") (pintype "passive+no_connect"))
    )
    (net (code "333") (name "unconnected-(U1E-TEST_GPIO[43]_4-PadD6)") (class "Default")
      (node (ref "U1") (pin "D6") (pinfunction "TEST_GPIO[43]_4_D6") (pintype "passive+no_connect"))
    )
    (net (code "334") (name "unconnected-(U1E-TEST_GPIO[44]_4-PadC5)") (class "Default")
      (node (ref "U1") (pin "C5") (pinfunction "TEST_GPIO[44]_4_C5") (pintype "passive+no_connect"))
    )
    (net (code "335") (name "unconnected-(U1E-TEST_GPIO[45]_4-PadB3)") (class "Default")
      (node (ref "U1") (pin "B3") (pinfunction "TEST_GPIO[45]_4_B3") (pintype "passive+no_connect"))
    )
    (net (code "336") (name "unconnected-(U1E-TEST_GPIO[46]_4-PadA3)") (class "Default")
      (node (ref "U1") (pin "A3") (pinfunction "TEST_GPIO[46]_4_A3") (pintype "passive+no_connect"))
    )
    (net (code "337") (name "unconnected-(U1E-TEST_GPIO[47]_4-PadD7)") (class "Default")
      (node (ref "U1") (pin "D7") (pinfunction "TEST_GPIO[47]_4_D7") (pintype "passive+no_connect"))
    )
    (net (code "338") (name "unconnected-(U1E-TEST_GPIO[48]_4-PadB5)") (class "Default")
      (node (ref "U1") (pin "B5") (pinfunction "TEST_GPIO[48]_4_B5") (pintype "passive+no_connect"))
    )
    (net (code "339") (name "unconnected-(U1E-TEST_GPIO[49]_4-PadA4)") (class "Default")
      (node (ref "U1") (pin "A4") (pinfunction "TEST_GPIO[49]_4_A4") (pintype "passive+no_connect"))
    )
    (net (code "340") (name "unconnected-(U1E-TEST_GPIO[50]_4-PadC7)") (class "Default")
      (node (ref "U1") (pin "C7") (pinfunction "TEST_GPIO[50]_4_C7") (pintype "passive+no_connect"))
    )
    (net (code "341") (name "unconnected-(U1E-TEST_GPIO[51]_4-PadB6)") (class "Default")
      (node (ref "U1") (pin "B6") (pinfunction "TEST_GPIO[51]_4_B6") (pintype "passive+no_connect"))
    )
    (net (code "342") (name "unconnected-(U1E-TEST_GPIO[52]_4-PadC13)") (class "Default")
      (node (ref "U1") (pin "C13") (pinfunction "TEST_GPIO[52]_4_C13") (pintype "passive+no_connect"))
    )
    (net (code "343") (name "unconnected-(U1E-TEST_GPIO[53]_4-PadB13)") (class "Default")
      (node (ref "U1") (pin "B13") (pinfunction "TEST_GPIO[53]_4_B13") (pintype "passive+no_connect"))
    )
    (net (code "344") (name "unconnected-(U1E-TEST_GPIO[54]_4-PadC14)") (class "Default")
      (node (ref "U1") (pin "C14") (pinfunction "TEST_GPIO[54]_4_C14") (pintype "passive+no_connect"))
    )
    (net (code "345") (name "unconnected-(U1E-TEST_GPIO[55]_4-PadD14)") (class "Default")
      (node (ref "U1") (pin "D14") (pinfunction "TEST_GPIO[55]_4_D14") (pintype "passive+no_connect"))
    )
    (net (code "346") (name "unconnected-(U1E-TEST_GPIO[56]_4-PadA13)") (class "Default")
      (node (ref "U1") (pin "A13") (pinfunction "TEST_GPIO[56]_4_A13") (pintype "passive+no_connect"))
    )
    (net (code "347") (name "unconnected-(U1E-TEST_GPIO[57]_4-PadA14)") (class "Default")
      (node (ref "U1") (pin "A14") (pinfunction "TEST_GPIO[57]_4_A14") (pintype "passive+no_connect"))
    )
    (net (code "348") (name "unconnected-(U1E-TEST_GPIO[58]_4-PadC15)") (class "Default")
      (node (ref "U1") (pin "C15") (pinfunction "TEST_GPIO[58]_4_C15") (pintype "passive+no_connect"))
    )
    (net (code "349") (name "unconnected-(U1E-TEST_GPIO[59]_4-PadD15)") (class "Default")
      (node (ref "U1") (pin "D15") (pinfunction "TEST_GPIO[59]_4_D15") (pintype "passive+no_connect"))
    )
    (net (code "350") (name "unconnected-(U1E-TEST_GPIO[60]_4-PadB15)") (class "Default")
      (node (ref "U1") (pin "B15") (pinfunction "TEST_GPIO[60]_4_B15") (pintype "passive+no_connect"))
    )
    (net (code "351") (name "unconnected-(U1E-TEST_GPIO[61]_4-PadA16)") (class "Default")
      (node (ref "U1") (pin "A16") (pinfunction "TEST_GPIO[61]_4_A16") (pintype "passive+no_connect"))
    )
    (net (code "352") (name "unconnected-(U1E-TEST_GPIO[62]_4-PadA15)") (class "Default")
      (node (ref "U1") (pin "A15") (pinfunction "TEST_GPIO[62]_4_A15") (pintype "passive+no_connect"))
    )
    (net (code "353") (name "unconnected-(U1E-TEST_GPIO[63]_4-PadB16)") (class "Default")
      (node (ref "U1") (pin "B16") (pinfunction "TEST_GPIO[63]_4_B16") (pintype "passive+no_connect"))
    )
    (net (code "354") (name "unconnected-(U1E-TEST_GPIO[64]_4-PadD16)") (class "Default")
      (node (ref "U1") (pin "D16") (pinfunction "TEST_GPIO[64]_4_D16") (pintype "passive+no_connect"))
    )
    (net (code "355") (name "unconnected-(U1E-TEST_GPIO[65]_4-PadC17)") (class "Default")
      (node (ref "U1") (pin "C17") (pinfunction "TEST_GPIO[65]_4_C17") (pintype "passive+no_connect"))
    )
    (net (code "356") (name "unconnected-(U1E-TEST_GPIO[66]_4-PadB17)") (class "Default")
      (node (ref "U1") (pin "B17") (pinfunction "TEST_GPIO[66]_4_B17") (pintype "passive+no_connect"))
    )
    (net (code "357") (name "unconnected-(U1E-TEST_GPIO[67]_4-PadD17)") (class "Default")
      (node (ref "U1") (pin "D17") (pinfunction "TEST_GPIO[67]_4_D17") (pintype "passive+no_connect"))
    )
    (net (code "358") (name "unconnected-(U1E-TEST_GPIO[68]_4-PadA18)") (class "Default")
      (node (ref "U1") (pin "A18") (pinfunction "TEST_GPIO[68]_4_A18") (pintype "passive+no_connect"))
    )
    (net (code "359") (name "unconnected-(U1E-TEST_GPIO[69]_4-PadC18)") (class "Default")
      (node (ref "U1") (pin "C18") (pinfunction "TEST_GPIO[69]_4_C18") (pintype "passive+no_connect"))
    )
    (net (code "360") (name "unconnected-(U1E-TEST_GPIO[70]_4-PadB18)") (class "Default")
      (node (ref "U1") (pin "B18") (pinfunction "TEST_GPIO[70]_4_B18") (pintype "passive+no_connect"))
    )
    (net (code "361") (name "unconnected-(U1E-TEST_GPIO[71]_4-PadE18)") (class "Default")
      (node (ref "U1") (pin "E18") (pinfunction "TEST_GPIO[71]_4_E18") (pintype "passive+no_connect"))
    )
  )
)
